# WordclockKopie.net
KiCad netlist of a schematic drawn in EAGLE
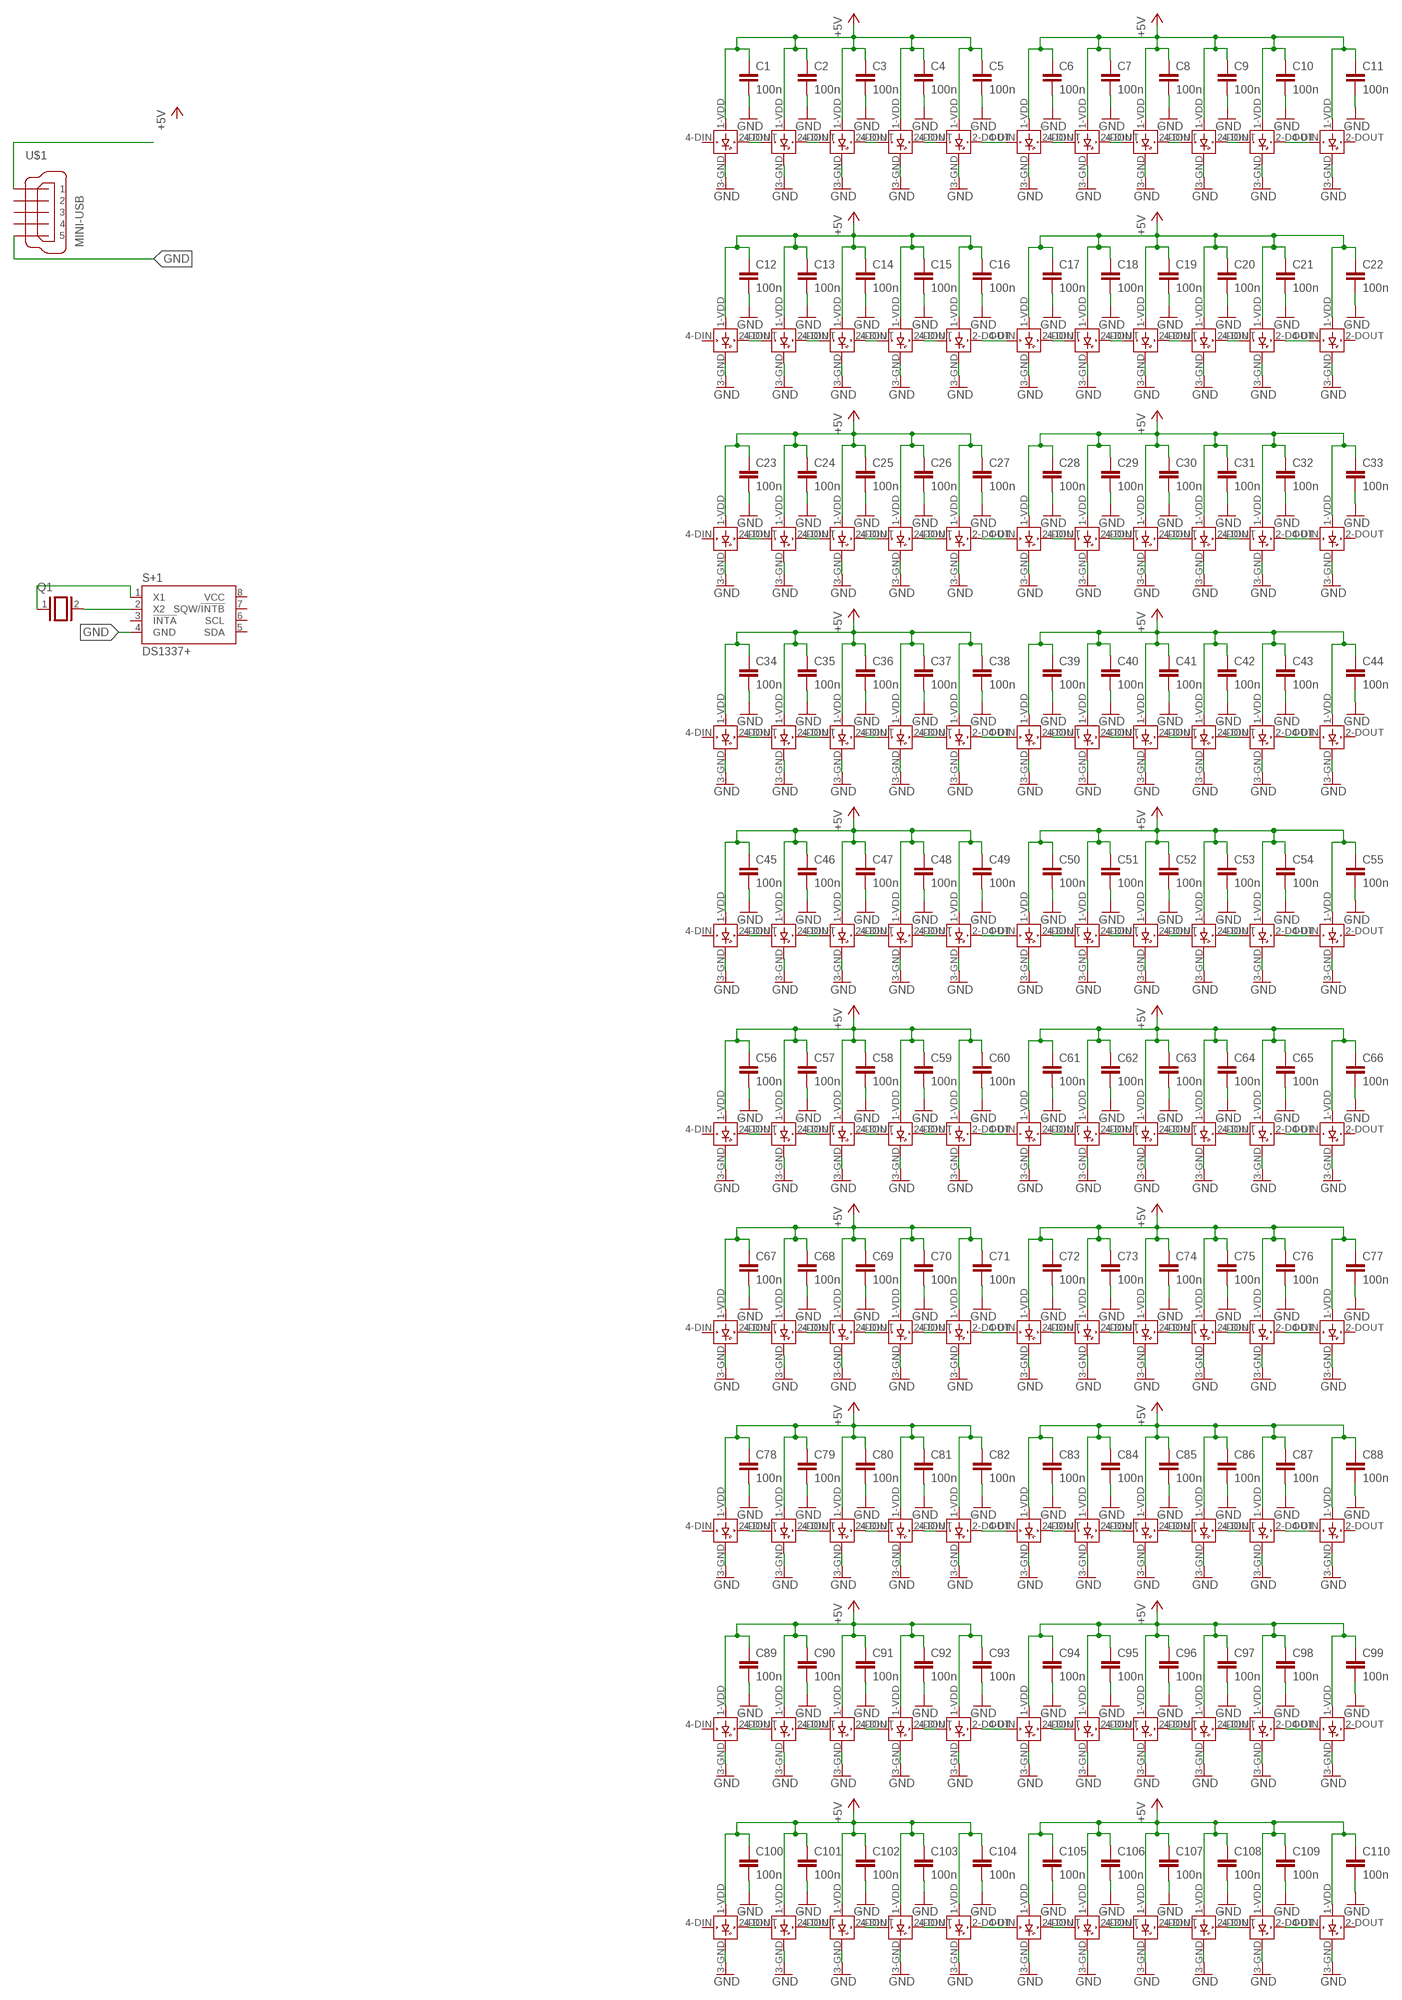
[diagram p0: schematic, sheet 1]

(export (version "E")
  (design (tool "Eeschema 10.0.6"))
  (components
    (comp (ref "C1")
      (value "100n")
      (footprint "eagle-import:C1310")
      (libsource (lib "eagle-import") (part "C-EUC1310"))
    )
    (comp (ref "C2")
      (value "100n")
      (footprint "eagle-import:C1310")
      (libsource (lib "eagle-import") (part "C-EUC1310"))
    )
    (comp (ref "C3")
      (value "100n")
      (footprint "eagle-import:C1310")
      (libsource (lib "eagle-import") (part "C-EUC1310"))
    )
    (comp (ref "C4")
      (value "100n")
      (footprint "eagle-import:C1310")
      (libsource (lib "eagle-import") (part "C-EUC1310"))
    )
    (comp (ref "C5")
      (value "100n")
      (footprint "eagle-import:C1310")
      (libsource (lib "eagle-import") (part "C-EUC1310"))
    )
    (comp (ref "C6")
      (value "100n")
      (footprint "eagle-import:C1310")
      (libsource (lib "eagle-import") (part "C-EUC1310"))
    )
    (comp (ref "C7")
      (value "100n")
      (footprint "eagle-import:C1310")
      (libsource (lib "eagle-import") (part "C-EUC1310"))
    )
    (comp (ref "C8")
      (value "100n")
      (footprint "eagle-import:C1310")
      (libsource (lib "eagle-import") (part "C-EUC1310"))
    )
    (comp (ref "C9")
      (value "100n")
      (footprint "eagle-import:C1310")
      (libsource (lib "eagle-import") (part "C-EUC1310"))
    )
    (comp (ref "C10")
      (value "100n")
      (footprint "eagle-import:C1310")
      (libsource (lib "eagle-import") (part "C-EUC1310"))
    )
    (comp (ref "C11")
      (value "100n")
      (footprint "eagle-import:C1310")
      (libsource (lib "eagle-import") (part "C-EUC1310"))
    )
    (comp (ref "C12")
      (value "100n")
      (footprint "eagle-import:C1310")
      (libsource (lib "eagle-import") (part "C-EUC1310"))
    )
    (comp (ref "C13")
      (value "100n")
      (footprint "eagle-import:C1310")
      (libsource (lib "eagle-import") (part "C-EUC1310"))
    )
    (comp (ref "C14")
      (value "100n")
      (footprint "eagle-import:C1310")
      (libsource (lib "eagle-import") (part "C-EUC1310"))
    )
    (comp (ref "C15")
      (value "100n")
      (footprint "eagle-import:C1310")
      (libsource (lib "eagle-import") (part "C-EUC1310"))
    )
    (comp (ref "C16")
      (value "100n")
      (footprint "eagle-import:C1310")
      (libsource (lib "eagle-import") (part "C-EUC1310"))
    )
    (comp (ref "C17")
      (value "100n")
      (footprint "eagle-import:C1310")
      (libsource (lib "eagle-import") (part "C-EUC1310"))
    )
    (comp (ref "C18")
      (value "100n")
      (footprint "eagle-import:C1310")
      (libsource (lib "eagle-import") (part "C-EUC1310"))
    )
    (comp (ref "C19")
      (value "100n")
      (footprint "eagle-import:C1310")
      (libsource (lib "eagle-import") (part "C-EUC1310"))
    )
    (comp (ref "C20")
      (value "100n")
      (footprint "eagle-import:C1310")
      (libsource (lib "eagle-import") (part "C-EUC1310"))
    )
    (comp (ref "C21")
      (value "100n")
      (footprint "eagle-import:C1310")
      (libsource (lib "eagle-import") (part "C-EUC1310"))
    )
    (comp (ref "C22")
      (value "100n")
      (footprint "eagle-import:C1310")
      (libsource (lib "eagle-import") (part "C-EUC1310"))
    )
    (comp (ref "C23")
      (value "100n")
      (footprint "eagle-import:C1310")
      (libsource (lib "eagle-import") (part "C-EUC1310"))
    )
    (comp (ref "C24")
      (value "100n")
      (footprint "eagle-import:C1310")
      (libsource (lib "eagle-import") (part "C-EUC1310"))
    )
    (comp (ref "C25")
      (value "100n")
      (footprint "eagle-import:C1310")
      (libsource (lib "eagle-import") (part "C-EUC1310"))
    )
    (comp (ref "C26")
      (value "100n")
      (footprint "eagle-import:C1310")
      (libsource (lib "eagle-import") (part "C-EUC1310"))
    )
    (comp (ref "C27")
      (value "100n")
      (footprint "eagle-import:C1310")
      (libsource (lib "eagle-import") (part "C-EUC1310"))
    )
    (comp (ref "C28")
      (value "100n")
      (footprint "eagle-import:C1310")
      (libsource (lib "eagle-import") (part "C-EUC1310"))
    )
    (comp (ref "C29")
      (value "100n")
      (footprint "eagle-import:C1310")
      (libsource (lib "eagle-import") (part "C-EUC1310"))
    )
    (comp (ref "C30")
      (value "100n")
      (footprint "eagle-import:C1310")
      (libsource (lib "eagle-import") (part "C-EUC1310"))
    )
    (comp (ref "C31")
      (value "100n")
      (footprint "eagle-import:C1310")
      (libsource (lib "eagle-import") (part "C-EUC1310"))
    )
    (comp (ref "C32")
      (value "100n")
      (footprint "eagle-import:C1310")
      (libsource (lib "eagle-import") (part "C-EUC1310"))
    )
    (comp (ref "C33")
      (value "100n")
      (footprint "eagle-import:C1310")
      (libsource (lib "eagle-import") (part "C-EUC1310"))
    )
    (comp (ref "C34")
      (value "100n")
      (footprint "eagle-import:C1310")
      (libsource (lib "eagle-import") (part "C-EUC1310"))
    )
    (comp (ref "C35")
      (value "100n")
      (footprint "eagle-import:C1310")
      (libsource (lib "eagle-import") (part "C-EUC1310"))
    )
    (comp (ref "C36")
      (value "100n")
      (footprint "eagle-import:C1310")
      (libsource (lib "eagle-import") (part "C-EUC1310"))
    )
    (comp (ref "C37")
      (value "100n")
      (footprint "eagle-import:C1310")
      (libsource (lib "eagle-import") (part "C-EUC1310"))
    )
    (comp (ref "C38")
      (value "100n")
      (footprint "eagle-import:C1310")
      (libsource (lib "eagle-import") (part "C-EUC1310"))
    )
    (comp (ref "C39")
      (value "100n")
      (footprint "eagle-import:C1310")
      (libsource (lib "eagle-import") (part "C-EUC1310"))
    )
    (comp (ref "C40")
      (value "100n")
      (footprint "eagle-import:C1310")
      (libsource (lib "eagle-import") (part "C-EUC1310"))
    )
    (comp (ref "C41")
      (value "100n")
      (footprint "eagle-import:C1310")
      (libsource (lib "eagle-import") (part "C-EUC1310"))
    )
    (comp (ref "C42")
      (value "100n")
      (footprint "eagle-import:C1310")
      (libsource (lib "eagle-import") (part "C-EUC1310"))
    )
    (comp (ref "C43")
      (value "100n")
      (footprint "eagle-import:C1310")
      (libsource (lib "eagle-import") (part "C-EUC1310"))
    )
    (comp (ref "C44")
      (value "100n")
      (footprint "eagle-import:C1310")
      (libsource (lib "eagle-import") (part "C-EUC1310"))
    )
    (comp (ref "C45")
      (value "100n")
      (footprint "eagle-import:C1310")
      (libsource (lib "eagle-import") (part "C-EUC1310"))
    )
    (comp (ref "C46")
      (value "100n")
      (footprint "eagle-import:C1310")
      (libsource (lib "eagle-import") (part "C-EUC1310"))
    )
    (comp (ref "C47")
      (value "100n")
      (footprint "eagle-import:C1310")
      (libsource (lib "eagle-import") (part "C-EUC1310"))
    )
    (comp (ref "C48")
      (value "100n")
      (footprint "eagle-import:C1310")
      (libsource (lib "eagle-import") (part "C-EUC1310"))
    )
    (comp (ref "C49")
      (value "100n")
      (footprint "eagle-import:C1310")
      (libsource (lib "eagle-import") (part "C-EUC1310"))
    )
    (comp (ref "C50")
      (value "100n")
      (footprint "eagle-import:C1310")
      (libsource (lib "eagle-import") (part "C-EUC1310"))
    )
    (comp (ref "C51")
      (value "100n")
      (footprint "eagle-import:C1310")
      (libsource (lib "eagle-import") (part "C-EUC1310"))
    )
    (comp (ref "C52")
      (value "100n")
      (footprint "eagle-import:C1310")
      (libsource (lib "eagle-import") (part "C-EUC1310"))
    )
    (comp (ref "C53")
      (value "100n")
      (footprint "eagle-import:C1310")
      (libsource (lib "eagle-import") (part "C-EUC1310"))
    )
    (comp (ref "C54")
      (value "100n")
      (footprint "eagle-import:C1310")
      (libsource (lib "eagle-import") (part "C-EUC1310"))
    )
    (comp (ref "C55")
      (value "100n")
      (footprint "eagle-import:C1310")
      (libsource (lib "eagle-import") (part "C-EUC1310"))
    )
    (comp (ref "C56")
      (value "100n")
      (footprint "eagle-import:C1310")
      (libsource (lib "eagle-import") (part "C-EUC1310"))
    )
    (comp (ref "C57")
      (value "100n")
      (footprint "eagle-import:C1310")
      (libsource (lib "eagle-import") (part "C-EUC1310"))
    )
    (comp (ref "C58")
      (value "100n")
      (footprint "eagle-import:C1310")
      (libsource (lib "eagle-import") (part "C-EUC1310"))
    )
    (comp (ref "C59")
      (value "100n")
      (footprint "eagle-import:C1310")
      (libsource (lib "eagle-import") (part "C-EUC1310"))
    )
    (comp (ref "C60")
      (value "100n")
      (footprint "eagle-import:C1310")
      (libsource (lib "eagle-import") (part "C-EUC1310"))
    )
    (comp (ref "C61")
      (value "100n")
      (footprint "eagle-import:C1310")
      (libsource (lib "eagle-import") (part "C-EUC1310"))
    )
    (comp (ref "C62")
      (value "100n")
      (footprint "eagle-import:C1310")
      (libsource (lib "eagle-import") (part "C-EUC1310"))
    )
    (comp (ref "C63")
      (value "100n")
      (footprint "eagle-import:C1310")
      (libsource (lib "eagle-import") (part "C-EUC1310"))
    )
    (comp (ref "C64")
      (value "100n")
      (footprint "eagle-import:C1310")
      (libsource (lib "eagle-import") (part "C-EUC1310"))
    )
    (comp (ref "C65")
      (value "100n")
      (footprint "eagle-import:C1310")
      (libsource (lib "eagle-import") (part "C-EUC1310"))
    )
    (comp (ref "C66")
      (value "100n")
      (footprint "eagle-import:C1310")
      (libsource (lib "eagle-import") (part "C-EUC1310"))
    )
    (comp (ref "C67")
      (value "100n")
      (footprint "eagle-import:C1310")
      (libsource (lib "eagle-import") (part "C-EUC1310"))
    )
    (comp (ref "C68")
      (value "100n")
      (footprint "eagle-import:C1310")
      (libsource (lib "eagle-import") (part "C-EUC1310"))
    )
    (comp (ref "C69")
      (value "100n")
      (footprint "eagle-import:C1310")
      (libsource (lib "eagle-import") (part "C-EUC1310"))
    )
    (comp (ref "C70")
      (value "100n")
      (footprint "eagle-import:C1310")
      (libsource (lib "eagle-import") (part "C-EUC1310"))
    )
    (comp (ref "C71")
      (value "100n")
      (footprint "eagle-import:C1310")
      (libsource (lib "eagle-import") (part "C-EUC1310"))
    )
    (comp (ref "C72")
      (value "100n")
      (footprint "eagle-import:C1310")
      (libsource (lib "eagle-import") (part "C-EUC1310"))
    )
    (comp (ref "C73")
      (value "100n")
      (footprint "eagle-import:C1310")
      (libsource (lib "eagle-import") (part "C-EUC1310"))
    )
    (comp (ref "C74")
      (value "100n")
      (footprint "eagle-import:C1310")
      (libsource (lib "eagle-import") (part "C-EUC1310"))
    )
    (comp (ref "C75")
      (value "100n")
      (footprint "eagle-import:C1310")
      (libsource (lib "eagle-import") (part "C-EUC1310"))
    )
    (comp (ref "C76")
      (value "100n")
      (footprint "eagle-import:C1310")
      (libsource (lib "eagle-import") (part "C-EUC1310"))
    )
    (comp (ref "C77")
      (value "100n")
      (footprint "eagle-import:C1310")
      (libsource (lib "eagle-import") (part "C-EUC1310"))
    )
    (comp (ref "C78")
      (value "100n")
      (footprint "eagle-import:C1310")
      (libsource (lib "eagle-import") (part "C-EUC1310"))
    )
    (comp (ref "C79")
      (value "100n")
      (footprint "eagle-import:C1310")
      (libsource (lib "eagle-import") (part "C-EUC1310"))
    )
    (comp (ref "C80")
      (value "100n")
      (footprint "eagle-import:C1310")
      (libsource (lib "eagle-import") (part "C-EUC1310"))
    )
    (comp (ref "C81")
      (value "100n")
      (footprint "eagle-import:C1310")
      (libsource (lib "eagle-import") (part "C-EUC1310"))
    )
    (comp (ref "C82")
      (value "100n")
      (footprint "eagle-import:C1310")
      (libsource (lib "eagle-import") (part "C-EUC1310"))
    )
    (comp (ref "C83")
      (value "100n")
      (footprint "eagle-import:C1310")
      (libsource (lib "eagle-import") (part "C-EUC1310"))
    )
    (comp (ref "C84")
      (value "100n")
      (footprint "eagle-import:C1310")
      (libsource (lib "eagle-import") (part "C-EUC1310"))
    )
    (comp (ref "C85")
      (value "100n")
      (footprint "eagle-import:C1310")
      (libsource (lib "eagle-import") (part "C-EUC1310"))
    )
    (comp (ref "C86")
      (value "100n")
      (footprint "eagle-import:C1310")
      (libsource (lib "eagle-import") (part "C-EUC1310"))
    )
    (comp (ref "C87")
      (value "100n")
      (footprint "eagle-import:C1310")
      (libsource (lib "eagle-import") (part "C-EUC1310"))
    )
    (comp (ref "C88")
      (value "100n")
      (footprint "eagle-import:C1310")
      (libsource (lib "eagle-import") (part "C-EUC1310"))
    )
    (comp (ref "C89")
      (value "100n")
      (footprint "eagle-import:C1310")
      (libsource (lib "eagle-import") (part "C-EUC1310"))
    )
    (comp (ref "C90")
      (value "100n")
      (footprint "eagle-import:C1310")
      (libsource (lib "eagle-import") (part "C-EUC1310"))
    )
    (comp (ref "C91")
      (value "100n")
      (footprint "eagle-import:C1310")
      (libsource (lib "eagle-import") (part "C-EUC1310"))
    )
    (comp (ref "C92")
      (value "100n")
      (footprint "eagle-import:C1310")
      (libsource (lib "eagle-import") (part "C-EUC1310"))
    )
    (comp (ref "C93")
      (value "100n")
      (footprint "eagle-import:C1310")
      (libsource (lib "eagle-import") (part "C-EUC1310"))
    )
    (comp (ref "C94")
      (value "100n")
      (footprint "eagle-import:C1310")
      (libsource (lib "eagle-import") (part "C-EUC1310"))
    )
    (comp (ref "C95")
      (value "100n")
      (footprint "eagle-import:C1310")
      (libsource (lib "eagle-import") (part "C-EUC1310"))
    )
    (comp (ref "C96")
      (value "100n")
      (footprint "eagle-import:C1310")
      (libsource (lib "eagle-import") (part "C-EUC1310"))
    )
    (comp (ref "C97")
      (value "100n")
      (footprint "eagle-import:C1310")
      (libsource (lib "eagle-import") (part "C-EUC1310"))
    )
    (comp (ref "C98")
      (value "100n")
      (footprint "eagle-import:C1310")
      (libsource (lib "eagle-import") (part "C-EUC1310"))
    )
    (comp (ref "C99")
      (value "100n")
      (footprint "eagle-import:C1310")
      (libsource (lib "eagle-import") (part "C-EUC1310"))
    )
    (comp (ref "C100")
      (value "100n")
      (footprint "eagle-import:C1310")
      (libsource (lib "eagle-import") (part "C-EUC1310"))
    )
    (comp (ref "C101")
      (value "100n")
      (footprint "eagle-import:C1310")
      (libsource (lib "eagle-import") (part "C-EUC1310"))
    )
    (comp (ref "C102")
      (value "100n")
      (footprint "eagle-import:C1310")
      (libsource (lib "eagle-import") (part "C-EUC1310"))
    )
    (comp (ref "C103")
      (value "100n")
      (footprint "eagle-import:C1310")
      (libsource (lib "eagle-import") (part "C-EUC1310"))
    )
    (comp (ref "C104")
      (value "100n")
      (footprint "eagle-import:C1310")
      (libsource (lib "eagle-import") (part "C-EUC1310"))
    )
    (comp (ref "C105")
      (value "100n")
      (footprint "eagle-import:C1310")
      (libsource (lib "eagle-import") (part "C-EUC1310"))
    )
    (comp (ref "C106")
      (value "100n")
      (footprint "eagle-import:C1310")
      (libsource (lib "eagle-import") (part "C-EUC1310"))
    )
    (comp (ref "C107")
      (value "100n")
      (footprint "eagle-import:C1310")
      (libsource (lib "eagle-import") (part "C-EUC1310"))
    )
    (comp (ref "C108")
      (value "100n")
      (footprint "eagle-import:C1310")
      (libsource (lib "eagle-import") (part "C-EUC1310"))
    )
    (comp (ref "C109")
      (value "100n")
      (footprint "eagle-import:C1310")
      (libsource (lib "eagle-import") (part "C-EUC1310"))
    )
    (comp (ref "C110")
      (value "100n")
      (footprint "eagle-import:C1310")
      (libsource (lib "eagle-import") (part "C-EUC1310"))
    )
    (comp (ref "L1")
      (value "WS2812B")
      (footprint "eagle-import:WS2812B")
      (libsource (lib "eagle-import") (part "WS2812B"))
    )
    (comp (ref "L2")
      (value "WS2812B")
      (footprint "eagle-import:WS2812B")
      (libsource (lib "eagle-import") (part "WS2812B"))
    )
    (comp (ref "L3")
      (value "WS2812B")
      (footprint "eagle-import:WS2812B")
      (libsource (lib "eagle-import") (part "WS2812B"))
    )
    (comp (ref "L4")
      (value "WS2812B")
      (footprint "eagle-import:WS2812B")
      (libsource (lib "eagle-import") (part "WS2812B"))
    )
    (comp (ref "L5")
      (value "WS2812B")
      (footprint "eagle-import:WS2812B")
      (libsource (lib "eagle-import") (part "WS2812B"))
    )
    (comp (ref "L6")
      (value "WS2812B")
      (footprint "eagle-import:WS2812B")
      (libsource (lib "eagle-import") (part "WS2812B"))
    )
    (comp (ref "L7")
      (value "WS2812B")
      (footprint "eagle-import:WS2812B")
      (libsource (lib "eagle-import") (part "WS2812B"))
    )
    (comp (ref "L8")
      (value "WS2812B")
      (footprint "eagle-import:WS2812B")
      (libsource (lib "eagle-import") (part "WS2812B"))
    )
    (comp (ref "L9")
      (value "WS2812B")
      (footprint "eagle-import:WS2812B")
      (libsource (lib "eagle-import") (part "WS2812B"))
    )
    (comp (ref "L10")
      (value "WS2812B")
      (footprint "eagle-import:WS2812B")
      (libsource (lib "eagle-import") (part "WS2812B"))
    )
    (comp (ref "L11")
      (value "WS2812B")
      (footprint "eagle-import:WS2812B")
      (libsource (lib "eagle-import") (part "WS2812B"))
    )
    (comp (ref "L12")
      (value "WS2812B")
      (footprint "eagle-import:WS2812B")
      (libsource (lib "eagle-import") (part "WS2812B"))
    )
    (comp (ref "L13")
      (value "WS2812B")
      (footprint "eagle-import:WS2812B")
      (libsource (lib "eagle-import") (part "WS2812B"))
    )
    (comp (ref "L14")
      (value "WS2812B")
      (footprint "eagle-import:WS2812B")
      (libsource (lib "eagle-import") (part "WS2812B"))
    )
    (comp (ref "L15")
      (value "WS2812B")
      (footprint "eagle-import:WS2812B")
      (libsource (lib "eagle-import") (part "WS2812B"))
    )
    (comp (ref "L16")
      (value "WS2812B")
      (footprint "eagle-import:WS2812B")
      (libsource (lib "eagle-import") (part "WS2812B"))
    )
    (comp (ref "L17")
      (value "WS2812B")
      (footprint "eagle-import:WS2812B")
      (libsource (lib "eagle-import") (part "WS2812B"))
    )
    (comp (ref "L18")
      (value "WS2812B")
      (footprint "eagle-import:WS2812B")
      (libsource (lib "eagle-import") (part "WS2812B"))
    )
    (comp (ref "L19")
      (value "WS2812B")
      (footprint "eagle-import:WS2812B")
      (libsource (lib "eagle-import") (part "WS2812B"))
    )
    (comp (ref "L20")
      (value "WS2812B")
      (footprint "eagle-import:WS2812B")
      (libsource (lib "eagle-import") (part "WS2812B"))
    )
    (comp (ref "L21")
      (value "WS2812B")
      (footprint "eagle-import:WS2812B")
      (libsource (lib "eagle-import") (part "WS2812B"))
    )
    (comp (ref "L22")
      (value "WS2812B")
      (footprint "eagle-import:WS2812B")
      (libsource (lib "eagle-import") (part "WS2812B"))
    )
    (comp (ref "L23")
      (value "WS2812B")
      (footprint "eagle-import:WS2812B")
      (libsource (lib "eagle-import") (part "WS2812B"))
    )
    (comp (ref "L24")
      (value "WS2812B")
      (footprint "eagle-import:WS2812B")
      (libsource (lib "eagle-import") (part "WS2812B"))
    )
    (comp (ref "L25")
      (value "WS2812B")
      (footprint "eagle-import:WS2812B")
      (libsource (lib "eagle-import") (part "WS2812B"))
    )
    (comp (ref "L26")
      (value "WS2812B")
      (footprint "eagle-import:WS2812B")
      (libsource (lib "eagle-import") (part "WS2812B"))
    )
    (comp (ref "L27")
      (value "WS2812B")
      (footprint "eagle-import:WS2812B")
      (libsource (lib "eagle-import") (part "WS2812B"))
    )
    (comp (ref "L28")
      (value "WS2812B")
      (footprint "eagle-import:WS2812B")
      (libsource (lib "eagle-import") (part "WS2812B"))
    )
    (comp (ref "L29")
      (value "WS2812B")
      (footprint "eagle-import:WS2812B")
      (libsource (lib "eagle-import") (part "WS2812B"))
    )
    (comp (ref "L30")
      (value "WS2812B")
      (footprint "eagle-import:WS2812B")
      (libsource (lib "eagle-import") (part "WS2812B"))
    )
    (comp (ref "L31")
      (value "WS2812B")
      (footprint "eagle-import:WS2812B")
      (libsource (lib "eagle-import") (part "WS2812B"))
    )
    (comp (ref "L32")
      (value "WS2812B")
      (footprint "eagle-import:WS2812B")
      (libsource (lib "eagle-import") (part "WS2812B"))
    )
    (comp (ref "L33")
      (value "WS2812B")
      (footprint "eagle-import:WS2812B")
      (libsource (lib "eagle-import") (part "WS2812B"))
    )
    (comp (ref "L34")
      (value "WS2812B")
      (footprint "eagle-import:WS2812B")
      (libsource (lib "eagle-import") (part "WS2812B"))
    )
    (comp (ref "L35")
      (value "WS2812B")
      (footprint "eagle-import:WS2812B")
      (libsource (lib "eagle-import") (part "WS2812B"))
    )
    (comp (ref "L36")
      (value "WS2812B")
      (footprint "eagle-import:WS2812B")
      (libsource (lib "eagle-import") (part "WS2812B"))
    )
    (comp (ref "L37")
      (value "WS2812B")
      (footprint "eagle-import:WS2812B")
      (libsource (lib "eagle-import") (part "WS2812B"))
    )
    (comp (ref "L38")
      (value "WS2812B")
      (footprint "eagle-import:WS2812B")
      (libsource (lib "eagle-import") (part "WS2812B"))
    )
    (comp (ref "L39")
      (value "WS2812B")
      (footprint "eagle-import:WS2812B")
      (libsource (lib "eagle-import") (part "WS2812B"))
    )
    (comp (ref "L40")
      (value "WS2812B")
      (footprint "eagle-import:WS2812B")
      (libsource (lib "eagle-import") (part "WS2812B"))
    )
    (comp (ref "L41")
      (value "WS2812B")
      (footprint "eagle-import:WS2812B")
      (libsource (lib "eagle-import") (part "WS2812B"))
    )
    (comp (ref "L42")
      (value "WS2812B")
      (footprint "eagle-import:WS2812B")
      (libsource (lib "eagle-import") (part "WS2812B"))
    )
    (comp (ref "L43")
      (value "WS2812B")
      (footprint "eagle-import:WS2812B")
      (libsource (lib "eagle-import") (part "WS2812B"))
    )
    (comp (ref "L44")
      (value "WS2812B")
      (footprint "eagle-import:WS2812B")
      (libsource (lib "eagle-import") (part "WS2812B"))
    )
    (comp (ref "L45")
      (value "WS2812B")
      (footprint "eagle-import:WS2812B")
      (libsource (lib "eagle-import") (part "WS2812B"))
    )
    (comp (ref "L46")
      (value "WS2812B")
      (footprint "eagle-import:WS2812B")
      (libsource (lib "eagle-import") (part "WS2812B"))
    )
    (comp (ref "L47")
      (value "WS2812B")
      (footprint "eagle-import:WS2812B")
      (libsource (lib "eagle-import") (part "WS2812B"))
    )
    (comp (ref "L48")
      (value "WS2812B")
      (footprint "eagle-import:WS2812B")
      (libsource (lib "eagle-import") (part "WS2812B"))
    )
    (comp (ref "L49")
      (value "WS2812B")
      (footprint "eagle-import:WS2812B")
      (libsource (lib "eagle-import") (part "WS2812B"))
    )
    (comp (ref "L50")
      (value "WS2812B")
      (footprint "eagle-import:WS2812B")
      (libsource (lib "eagle-import") (part "WS2812B"))
    )
    (comp (ref "L51")
      (value "WS2812B")
      (footprint "eagle-import:WS2812B")
      (libsource (lib "eagle-import") (part "WS2812B"))
    )
    (comp (ref "L52")
      (value "WS2812B")
      (footprint "eagle-import:WS2812B")
      (libsource (lib "eagle-import") (part "WS2812B"))
    )
    (comp (ref "L53")
      (value "WS2812B")
      (footprint "eagle-import:WS2812B")
      (libsource (lib "eagle-import") (part "WS2812B"))
    )
    (comp (ref "L54")
      (value "WS2812B")
      (footprint "eagle-import:WS2812B")
      (libsource (lib "eagle-import") (part "WS2812B"))
    )
    (comp (ref "L55")
      (value "WS2812B")
      (footprint "eagle-import:WS2812B")
      (libsource (lib "eagle-import") (part "WS2812B"))
    )
    (comp (ref "L56")
      (value "WS2812B")
      (footprint "eagle-import:WS2812B")
      (libsource (lib "eagle-import") (part "WS2812B"))
    )
    (comp (ref "L57")
      (value "WS2812B")
      (footprint "eagle-import:WS2812B")
      (libsource (lib "eagle-import") (part "WS2812B"))
    )
    (comp (ref "L58")
      (value "WS2812B")
      (footprint "eagle-import:WS2812B")
      (libsource (lib "eagle-import") (part "WS2812B"))
    )
    (comp (ref "L59")
      (value "WS2812B")
      (footprint "eagle-import:WS2812B")
      (libsource (lib "eagle-import") (part "WS2812B"))
    )
    (comp (ref "L60")
      (value "WS2812B")
      (footprint "eagle-import:WS2812B")
      (libsource (lib "eagle-import") (part "WS2812B"))
    )
    (comp (ref "L61")
      (value "WS2812B")
      (footprint "eagle-import:WS2812B")
      (libsource (lib "eagle-import") (part "WS2812B"))
    )
    (comp (ref "L62")
      (value "WS2812B")
      (footprint "eagle-import:WS2812B")
      (libsource (lib "eagle-import") (part "WS2812B"))
    )
    (comp (ref "L63")
      (value "WS2812B")
      (footprint "eagle-import:WS2812B")
      (libsource (lib "eagle-import") (part "WS2812B"))
    )
    (comp (ref "L64")
      (value "WS2812B")
      (footprint "eagle-import:WS2812B")
      (libsource (lib "eagle-import") (part "WS2812B"))
    )
    (comp (ref "L65")
      (value "WS2812B")
      (footprint "eagle-import:WS2812B")
      (libsource (lib "eagle-import") (part "WS2812B"))
    )
    (comp (ref "L66")
      (value "WS2812B")
      (footprint "eagle-import:WS2812B")
      (libsource (lib "eagle-import") (part "WS2812B"))
    )
    (comp (ref "L67")
      (value "WS2812B")
      (footprint "eagle-import:WS2812B")
      (libsource (lib "eagle-import") (part "WS2812B"))
    )
    (comp (ref "L68")
      (value "WS2812B")
      (footprint "eagle-import:WS2812B")
      (libsource (lib "eagle-import") (part "WS2812B"))
    )
    (comp (ref "L69")
      (value "WS2812B")
      (footprint "eagle-import:WS2812B")
      (libsource (lib "eagle-import") (part "WS2812B"))
    )
    (comp (ref "L70")
      (value "WS2812B")
      (footprint "eagle-import:WS2812B")
      (libsource (lib "eagle-import") (part "WS2812B"))
    )
    (comp (ref "L71")
      (value "WS2812B")
      (footprint "eagle-import:WS2812B")
      (libsource (lib "eagle-import") (part "WS2812B"))
    )
    (comp (ref "L72")
      (value "WS2812B")
      (footprint "eagle-import:WS2812B")
      (libsource (lib "eagle-import") (part "WS2812B"))
    )
    (comp (ref "L73")
      (value "WS2812B")
      (footprint "eagle-import:WS2812B")
      (libsource (lib "eagle-import") (part "WS2812B"))
    )
    (comp (ref "L74")
      (value "WS2812B")
      (footprint "eagle-import:WS2812B")
      (libsource (lib "eagle-import") (part "WS2812B"))
    )
    (comp (ref "L75")
      (value "WS2812B")
      (footprint "eagle-import:WS2812B")
      (libsource (lib "eagle-import") (part "WS2812B"))
    )
    (comp (ref "L76")
      (value "WS2812B")
      (footprint "eagle-import:WS2812B")
      (libsource (lib "eagle-import") (part "WS2812B"))
    )
    (comp (ref "L77")
      (value "WS2812B")
      (footprint "eagle-import:WS2812B")
      (libsource (lib "eagle-import") (part "WS2812B"))
    )
    (comp (ref "L78")
      (value "WS2812B")
      (footprint "eagle-import:WS2812B")
      (libsource (lib "eagle-import") (part "WS2812B"))
    )
    (comp (ref "L79")
      (value "WS2812B")
      (footprint "eagle-import:WS2812B")
      (libsource (lib "eagle-import") (part "WS2812B"))
    )
    (comp (ref "L80")
      (value "WS2812B")
      (footprint "eagle-import:WS2812B")
      (libsource (lib "eagle-import") (part "WS2812B"))
    )
    (comp (ref "L81")
      (value "WS2812B")
      (footprint "eagle-import:WS2812B")
      (libsource (lib "eagle-import") (part "WS2812B"))
    )
    (comp (ref "L82")
      (value "WS2812B")
      (footprint "eagle-import:WS2812B")
      (libsource (lib "eagle-import") (part "WS2812B"))
    )
    (comp (ref "L83")
      (value "WS2812B")
      (footprint "eagle-import:WS2812B")
      (libsource (lib "eagle-import") (part "WS2812B"))
    )
    (comp (ref "L84")
      (value "WS2812B")
      (footprint "eagle-import:WS2812B")
      (libsource (lib "eagle-import") (part "WS2812B"))
    )
    (comp (ref "L85")
      (value "WS2812B")
      (footprint "eagle-import:WS2812B")
      (libsource (lib "eagle-import") (part "WS2812B"))
    )
    (comp (ref "L86")
      (value "WS2812B")
      (footprint "eagle-import:WS2812B")
      (libsource (lib "eagle-import") (part "WS2812B"))
    )
    (comp (ref "L87")
      (value "WS2812B")
      (footprint "eagle-import:WS2812B")
      (libsource (lib "eagle-import") (part "WS2812B"))
    )
    (comp (ref "L88")
      (value "WS2812B")
      (footprint "eagle-import:WS2812B")
      (libsource (lib "eagle-import") (part "WS2812B"))
    )
    (comp (ref "L89")
      (value "WS2812B")
      (footprint "eagle-import:WS2812B")
      (libsource (lib "eagle-import") (part "WS2812B"))
    )
    (comp (ref "L90")
      (value "WS2812B")
      (footprint "eagle-import:WS2812B")
      (libsource (lib "eagle-import") (part "WS2812B"))
    )
    (comp (ref "L91")
      (value "WS2812B")
      (footprint "eagle-import:WS2812B")
      (libsource (lib "eagle-import") (part "WS2812B"))
    )
    (comp (ref "L92")
      (value "WS2812B")
      (footprint "eagle-import:WS2812B")
      (libsource (lib "eagle-import") (part "WS2812B"))
    )
    (comp (ref "L93")
      (value "WS2812B")
      (footprint "eagle-import:WS2812B")
      (libsource (lib "eagle-import") (part "WS2812B"))
    )
    (comp (ref "L94")
      (value "WS2812B")
      (footprint "eagle-import:WS2812B")
      (libsource (lib "eagle-import") (part "WS2812B"))
    )
    (comp (ref "L95")
      (value "WS2812B")
      (footprint "eagle-import:WS2812B")
      (libsource (lib "eagle-import") (part "WS2812B"))
    )
    (comp (ref "L96")
      (value "WS2812B")
      (footprint "eagle-import:WS2812B")
      (libsource (lib "eagle-import") (part "WS2812B"))
    )
    (comp (ref "L97")
      (value "WS2812B")
      (footprint "eagle-import:WS2812B")
      (libsource (lib "eagle-import") (part "WS2812B"))
    )
    (comp (ref "L98")
      (value "WS2812B")
      (footprint "eagle-import:WS2812B")
      (libsource (lib "eagle-import") (part "WS2812B"))
    )
    (comp (ref "L99")
      (value "WS2812B")
      (footprint "eagle-import:WS2812B")
      (libsource (lib "eagle-import") (part "WS2812B"))
    )
    (comp (ref "L100")
      (value "WS2812B")
      (footprint "eagle-import:WS2812B")
      (libsource (lib "eagle-import") (part "WS2812B"))
    )
    (comp (ref "L101")
      (value "WS2812B")
      (footprint "eagle-import:WS2812B")
      (libsource (lib "eagle-import") (part "WS2812B"))
    )
    (comp (ref "L102")
      (value "WS2812B")
      (footprint "eagle-import:WS2812B")
      (libsource (lib "eagle-import") (part "WS2812B"))
    )
    (comp (ref "L103")
      (value "WS2812B")
      (footprint "eagle-import:WS2812B")
      (libsource (lib "eagle-import") (part "WS2812B"))
    )
    (comp (ref "L104")
      (value "WS2812B")
      (footprint "eagle-import:WS2812B")
      (libsource (lib "eagle-import") (part "WS2812B"))
    )
    (comp (ref "L105")
      (value "WS2812B")
      (footprint "eagle-import:WS2812B")
      (libsource (lib "eagle-import") (part "WS2812B"))
    )
    (comp (ref "L106")
      (value "WS2812B")
      (footprint "eagle-import:WS2812B")
      (libsource (lib "eagle-import") (part "WS2812B"))
    )
    (comp (ref "L107")
      (value "WS2812B")
      (footprint "eagle-import:WS2812B")
      (libsource (lib "eagle-import") (part "WS2812B"))
    )
    (comp (ref "L108")
      (value "WS2812B")
      (footprint "eagle-import:WS2812B")
      (libsource (lib "eagle-import") (part "WS2812B"))
    )
    (comp (ref "L109")
      (value "WS2812B")
      (footprint "eagle-import:WS2812B")
      (libsource (lib "eagle-import") (part "WS2812B"))
    )
    (comp (ref "L110")
      (value "WS2812B")
      (footprint "eagle-import:WS2812B")
      (libsource (lib "eagle-import") (part "WS2812B"))
    )
    (comp (ref "Q1")
      (value "XTAL")
      (footprint "eagle-import:Q")
      (libsource (lib "eagle-import") (part "XTAL"))
    )
    (comp (ref "S+1")
      (value "DS1337+")
      (footprint "eagle-import:DIL8")
      (libsource (lib "eagle-import") (part "DS1337+"))
    )
    (comp (ref "U$1")
      (value "MINI-USB")
      (footprint "eagle-import:MINI-USB")
      (libsource (lib "eagle-import") (part "MINI-USB"))
    )
  )
  (nets
    (net (code "1") (name "+5V") (class "Default")
      (node (ref "C1") (pin "1") (pinfunction "1_1") (pintype "passive"))
      (node (ref "C10") (pin "1") (pinfunction "1_1") (pintype "passive"))
      (node (ref "C100") (pin "1") (pinfunction "1_1") (pintype "passive"))
      (node (ref "C101") (pin "1") (pinfunction "1_1") (pintype "passive"))
      (node (ref "C102") (pin "1") (pinfunction "1_1") (pintype "passive"))
      (node (ref "C103") (pin "1") (pinfunction "1_1") (pintype "passive"))
      (node (ref "C104") (pin "1") (pinfunction "1_1") (pintype "passive"))
      (node (ref "C105") (pin "1") (pinfunction "1_1") (pintype "passive"))
      (node (ref "C106") (pin "1") (pinfunction "1_1") (pintype "passive"))
      (node (ref "C107") (pin "1") (pinfunction "1_1") (pintype "passive"))
      (node (ref "C108") (pin "1") (pinfunction "1_1") (pintype "passive"))
      (node (ref "C109") (pin "1") (pinfunction "1_1") (pintype "passive"))
      (node (ref "C11") (pin "1") (pinfunction "1_1") (pintype "passive"))
      (node (ref "C110") (pin "1") (pinfunction "1_1") (pintype "passive"))
      (node (ref "C12") (pin "1") (pinfunction "1_1") (pintype "passive"))
      (node (ref "C13") (pin "1") (pinfunction "1_1") (pintype "passive"))
      (node (ref "C14") (pin "1") (pinfunction "1_1") (pintype "passive"))
      (node (ref "C15") (pin "1") (pinfunction "1_1") (pintype "passive"))
      (node (ref "C16") (pin "1") (pinfunction "1_1") (pintype "passive"))
      (node (ref "C17") (pin "1") (pinfunction "1_1") (pintype "passive"))
      (node (ref "C18") (pin "1") (pinfunction "1_1") (pintype "passive"))
      (node (ref "C19") (pin "1") (pinfunction "1_1") (pintype "passive"))
      (node (ref "C2") (pin "1") (pinfunction "1_1") (pintype "passive"))
      (node (ref "C20") (pin "1") (pinfunction "1_1") (pintype "passive"))
      (node (ref "C21") (pin "1") (pinfunction "1_1") (pintype "passive"))
      (node (ref "C22") (pin "1") (pinfunction "1_1") (pintype "passive"))
      (node (ref "C23") (pin "1") (pinfunction "1_1") (pintype "passive"))
      (node (ref "C24") (pin "1") (pinfunction "1_1") (pintype "passive"))
      (node (ref "C25") (pin "1") (pinfunction "1_1") (pintype "passive"))
      (node (ref "C26") (pin "1") (pinfunction "1_1") (pintype "passive"))
      (node (ref "C27") (pin "1") (pinfunction "1_1") (pintype "passive"))
      (node (ref "C28") (pin "1") (pinfunction "1_1") (pintype "passive"))
      (node (ref "C29") (pin "1") (pinfunction "1_1") (pintype "passive"))
      (node (ref "C3") (pin "1") (pinfunction "1_1") (pintype "passive"))
      (node (ref "C30") (pin "1") (pinfunction "1_1") (pintype "passive"))
      (node (ref "C31") (pin "1") (pinfunction "1_1") (pintype "passive"))
      (node (ref "C32") (pin "1") (pinfunction "1_1") (pintype "passive"))
      (node (ref "C33") (pin "1") (pinfunction "1_1") (pintype "passive"))
      (node (ref "C34") (pin "1") (pinfunction "1_1") (pintype "passive"))
      (node (ref "C35") (pin "1") (pinfunction "1_1") (pintype "passive"))
      (node (ref "C36") (pin "1") (pinfunction "1_1") (pintype "passive"))
      (node (ref "C37") (pin "1") (pinfunction "1_1") (pintype "passive"))
      (node (ref "C38") (pin "1") (pinfunction "1_1") (pintype "passive"))
      (node (ref "C39") (pin "1") (pinfunction "1_1") (pintype "passive"))
      (node (ref "C4") (pin "1") (pinfunction "1_1") (pintype "passive"))
      (node (ref "C40") (pin "1") (pinfunction "1_1") (pintype "passive"))
      (node (ref "C41") (pin "1") (pinfunction "1_1") (pintype "passive"))
      (node (ref "C42") (pin "1") (pinfunction "1_1") (pintype "passive"))
      (node (ref "C43") (pin "1") (pinfunction "1_1") (pintype "passive"))
      (node (ref "C44") (pin "1") (pinfunction "1_1") (pintype "passive"))
      (node (ref "C45") (pin "1") (pinfunction "1_1") (pintype "passive"))
      (node (ref "C46") (pin "1") (pinfunction "1_1") (pintype "passive"))
      (node (ref "C47") (pin "1") (pinfunction "1_1") (pintype "passive"))
      (node (ref "C48") (pin "1") (pinfunction "1_1") (pintype "passive"))
      (node (ref "C49") (pin "1") (pinfunction "1_1") (pintype "passive"))
      (node (ref "C5") (pin "1") (pinfunction "1_1") (pintype "passive"))
      (node (ref "C50") (pin "1") (pinfunction "1_1") (pintype "passive"))
      (node (ref "C51") (pin "1") (pinfunction "1_1") (pintype "passive"))
      (node (ref "C52") (pin "1") (pinfunction "1_1") (pintype "passive"))
      (node (ref "C53") (pin "1") (pinfunction "1_1") (pintype "passive"))
      (node (ref "C54") (pin "1") (pinfunction "1_1") (pintype "passive"))
      (node (ref "C55") (pin "1") (pinfunction "1_1") (pintype "passive"))
      (node (ref "C56") (pin "1") (pinfunction "1_1") (pintype "passive"))
      (node (ref "C57") (pin "1") (pinfunction "1_1") (pintype "passive"))
      (node (ref "C58") (pin "1") (pinfunction "1_1") (pintype "passive"))
      (node (ref "C59") (pin "1") (pinfunction "1_1") (pintype "passive"))
      (node (ref "C6") (pin "1") (pinfunction "1_1") (pintype "passive"))
      (node (ref "C60") (pin "1") (pinfunction "1_1") (pintype "passive"))
      (node (ref "C61") (pin "1") (pinfunction "1_1") (pintype "passive"))
      (node (ref "C62") (pin "1") (pinfunction "1_1") (pintype "passive"))
      (node (ref "C63") (pin "1") (pinfunction "1_1") (pintype "passive"))
      (node (ref "C64") (pin "1") (pinfunction "1_1") (pintype "passive"))
      (node (ref "C65") (pin "1") (pinfunction "1_1") (pintype "passive"))
      (node (ref "C66") (pin "1") (pinfunction "1_1") (pintype "passive"))
      (node (ref "C67") (pin "1") (pinfunction "1_1") (pintype "passive"))
      (node (ref "C68") (pin "1") (pinfunction "1_1") (pintype "passive"))
      (node (ref "C69") (pin "1") (pinfunction "1_1") (pintype "passive"))
      (node (ref "C7") (pin "1") (pinfunction "1_1") (pintype "passive"))
      (node (ref "C70") (pin "1") (pinfunction "1_1") (pintype "passive"))
      (node (ref "C71") (pin "1") (pinfunction "1_1") (pintype "passive"))
      (node (ref "C72") (pin "1") (pinfunction "1_1") (pintype "passive"))
      (node (ref "C73") (pin "1") (pinfunction "1_1") (pintype "passive"))
      (node (ref "C74") (pin "1") (pinfunction "1_1") (pintype "passive"))
      (node (ref "C75") (pin "1") (pinfunction "1_1") (pintype "passive"))
      (node (ref "C76") (pin "1") (pinfunction "1_1") (pintype "passive"))
      (node (ref "C77") (pin "1") (pinfunction "1_1") (pintype "passive"))
      (node (ref "C78") (pin "1") (pinfunction "1_1") (pintype "passive"))
      (node (ref "C79") (pin "1") (pinfunction "1_1") (pintype "passive"))
      (node (ref "C8") (pin "1") (pinfunction "1_1") (pintype "passive"))
      (node (ref "C80") (pin "1") (pinfunction "1_1") (pintype "passive"))
      (node (ref "C81") (pin "1") (pinfunction "1_1") (pintype "passive"))
      (node (ref "C82") (pin "1") (pinfunction "1_1") (pintype "passive"))
      (node (ref "C83") (pin "1") (pinfunction "1_1") (pintype "passive"))
      (node (ref "C84") (pin "1") (pinfunction "1_1") (pintype "passive"))
      (node (ref "C85") (pin "1") (pinfunction "1_1") (pintype "passive"))
      (node (ref "C86") (pin "1") (pinfunction "1_1") (pintype "passive"))
      (node (ref "C87") (pin "1") (pinfunction "1_1") (pintype "passive"))
      (node (ref "C88") (pin "1") (pinfunction "1_1") (pintype "passive"))
      (node (ref "C89") (pin "1") (pinfunction "1_1") (pintype "passive"))
      (node (ref "C9") (pin "1") (pinfunction "1_1") (pintype "passive"))
      (node (ref "C90") (pin "1") (pinfunction "1_1") (pintype "passive"))
      (node (ref "C91") (pin "1") (pinfunction "1_1") (pintype "passive"))
      (node (ref "C92") (pin "1") (pinfunction "1_1") (pintype "passive"))
      (node (ref "C93") (pin "1") (pinfunction "1_1") (pintype "passive"))
      (node (ref "C94") (pin "1") (pinfunction "1_1") (pintype "passive"))
      (node (ref "C95") (pin "1") (pinfunction "1_1") (pintype "passive"))
      (node (ref "C96") (pin "1") (pinfunction "1_1") (pintype "passive"))
      (node (ref "C97") (pin "1") (pinfunction "1_1") (pintype "passive"))
      (node (ref "C98") (pin "1") (pinfunction "1_1") (pintype "passive"))
      (node (ref "C99") (pin "1") (pinfunction "1_1") (pintype "passive"))
      (node (ref "L1") (pin "1-VDD") (pinfunction "VDD_1-VDD") (pintype "bidirectional"))
      (node (ref "L10") (pin "1-VDD") (pinfunction "VDD_1-VDD") (pintype "bidirectional"))
      (node (ref "L100") (pin "1-VDD") (pinfunction "VDD_1-VDD") (pintype "bidirectional"))
      (node (ref "L101") (pin "1-VDD") (pinfunction "VDD_1-VDD") (pintype "bidirectional"))
      (node (ref "L102") (pin "1-VDD") (pinfunction "VDD_1-VDD") (pintype "bidirectional"))
      (node (ref "L103") (pin "1-VDD") (pinfunction "VDD_1-VDD") (pintype "bidirectional"))
      (node (ref "L104") (pin "1-VDD") (pinfunction "VDD_1-VDD") (pintype "bidirectional"))
      (node (ref "L105") (pin "1-VDD") (pinfunction "VDD_1-VDD") (pintype "bidirectional"))
      (node (ref "L106") (pin "1-VDD") (pinfunction "VDD_1-VDD") (pintype "bidirectional"))
      (node (ref "L107") (pin "1-VDD") (pinfunction "VDD_1-VDD") (pintype "bidirectional"))
      (node (ref "L108") (pin "1-VDD") (pinfunction "VDD_1-VDD") (pintype "bidirectional"))
      (node (ref "L109") (pin "1-VDD") (pinfunction "VDD_1-VDD") (pintype "bidirectional"))
      (node (ref "L11") (pin "1-VDD") (pinfunction "VDD_1-VDD") (pintype "bidirectional"))
      (node (ref "L110") (pin "1-VDD") (pinfunction "VDD_1-VDD") (pintype "bidirectional"))
      (node (ref "L12") (pin "1-VDD") (pinfunction "VDD_1-VDD") (pintype "bidirectional"))
      (node (ref "L13") (pin "1-VDD") (pinfunction "VDD_1-VDD") (pintype "bidirectional"))
      (node (ref "L14") (pin "1-VDD") (pinfunction "VDD_1-VDD") (pintype "bidirectional"))
      (node (ref "L15") (pin "1-VDD") (pinfunction "VDD_1-VDD") (pintype "bidirectional"))
      (node (ref "L16") (pin "1-VDD") (pinfunction "VDD_1-VDD") (pintype "bidirectional"))
      (node (ref "L17") (pin "1-VDD") (pinfunction "VDD_1-VDD") (pintype "bidirectional"))
      (node (ref "L18") (pin "1-VDD") (pinfunction "VDD_1-VDD") (pintype "bidirectional"))
      (node (ref "L19") (pin "1-VDD") (pinfunction "VDD_1-VDD") (pintype "bidirectional"))
      (node (ref "L2") (pin "1-VDD") (pinfunction "VDD_1-VDD") (pintype "bidirectional"))
      (node (ref "L20") (pin "1-VDD") (pinfunction "VDD_1-VDD") (pintype "bidirectional"))
      (node (ref "L21") (pin "1-VDD") (pinfunction "VDD_1-VDD") (pintype "bidirectional"))
      (node (ref "L22") (pin "1-VDD") (pinfunction "VDD_1-VDD") (pintype "bidirectional"))
      (node (ref "L23") (pin "1-VDD") (pinfunction "VDD_1-VDD") (pintype "bidirectional"))
      (node (ref "L24") (pin "1-VDD") (pinfunction "VDD_1-VDD") (pintype "bidirectional"))
      (node (ref "L25") (pin "1-VDD") (pinfunction "VDD_1-VDD") (pintype "bidirectional"))
      (node (ref "L26") (pin "1-VDD") (pinfunction "VDD_1-VDD") (pintype "bidirectional"))
      (node (ref "L27") (pin "1-VDD") (pinfunction "VDD_1-VDD") (pintype "bidirectional"))
      (node (ref "L28") (pin "1-VDD") (pinfunction "VDD_1-VDD") (pintype "bidirectional"))
      (node (ref "L29") (pin "1-VDD") (pinfunction "VDD_1-VDD") (pintype "bidirectional"))
      (node (ref "L3") (pin "1-VDD") (pinfunction "VDD_1-VDD") (pintype "bidirectional"))
      (node (ref "L30") (pin "1-VDD") (pinfunction "VDD_1-VDD") (pintype "bidirectional"))
      (node (ref "L31") (pin "1-VDD") (pinfunction "VDD_1-VDD") (pintype "bidirectional"))
      (node (ref "L32") (pin "1-VDD") (pinfunction "VDD_1-VDD") (pintype "bidirectional"))
      (node (ref "L33") (pin "1-VDD") (pinfunction "VDD_1-VDD") (pintype "bidirectional"))
      (node (ref "L34") (pin "1-VDD") (pinfunction "VDD_1-VDD") (pintype "bidirectional"))
      (node (ref "L35") (pin "1-VDD") (pinfunction "VDD_1-VDD") (pintype "bidirectional"))
      (node (ref "L36") (pin "1-VDD") (pinfunction "VDD_1-VDD") (pintype "bidirectional"))
      (node (ref "L37") (pin "1-VDD") (pinfunction "VDD_1-VDD") (pintype "bidirectional"))
      (node (ref "L38") (pin "1-VDD") (pinfunction "VDD_1-VDD") (pintype "bidirectional"))
      (node (ref "L39") (pin "1-VDD") (pinfunction "VDD_1-VDD") (pintype "bidirectional"))
      (node (ref "L4") (pin "1-VDD") (pinfunction "VDD_1-VDD") (pintype "bidirectional"))
      (node (ref "L40") (pin "1-VDD") (pinfunction "VDD_1-VDD") (pintype "bidirectional"))
      (node (ref "L41") (pin "1-VDD") (pinfunction "VDD_1-VDD") (pintype "bidirectional"))
      (node (ref "L42") (pin "1-VDD") (pinfunction "VDD_1-VDD") (pintype "bidirectional"))
      (node (ref "L43") (pin "1-VDD") (pinfunction "VDD_1-VDD") (pintype "bidirectional"))
      (node (ref "L44") (pin "1-VDD") (pinfunction "VDD_1-VDD") (pintype "bidirectional"))
      (node (ref "L45") (pin "1-VDD") (pinfunction "VDD_1-VDD") (pintype "bidirectional"))
      (node (ref "L46") (pin "1-VDD") (pinfunction "VDD_1-VDD") (pintype "bidirectional"))
      (node (ref "L47") (pin "1-VDD") (pinfunction "VDD_1-VDD") (pintype "bidirectional"))
      (node (ref "L48") (pin "1-VDD") (pinfunction "VDD_1-VDD") (pintype "bidirectional"))
      (node (ref "L49") (pin "1-VDD") (pinfunction "VDD_1-VDD") (pintype "bidirectional"))
      (node (ref "L5") (pin "1-VDD") (pinfunction "VDD_1-VDD") (pintype "bidirectional"))
      (node (ref "L50") (pin "1-VDD") (pinfunction "VDD_1-VDD") (pintype "bidirectional"))
      (node (ref "L51") (pin "1-VDD") (pinfunction "VDD_1-VDD") (pintype "bidirectional"))
      (node (ref "L52") (pin "1-VDD") (pinfunction "VDD_1-VDD") (pintype "bidirectional"))
      (node (ref "L53") (pin "1-VDD") (pinfunction "VDD_1-VDD") (pintype "bidirectional"))
      (node (ref "L54") (pin "1-VDD") (pinfunction "VDD_1-VDD") (pintype "bidirectional"))
      (node (ref "L55") (pin "1-VDD") (pinfunction "VDD_1-VDD") (pintype "bidirectional"))
      (node (ref "L56") (pin "1-VDD") (pinfunction "VDD_1-VDD") (pintype "bidirectional"))
      (node (ref "L57") (pin "1-VDD") (pinfunction "VDD_1-VDD") (pintype "bidirectional"))
      (node (ref "L58") (pin "1-VDD") (pinfunction "VDD_1-VDD") (pintype "bidirectional"))
      (node (ref "L59") (pin "1-VDD") (pinfunction "VDD_1-VDD") (pintype "bidirectional"))
      (node (ref "L6") (pin "1-VDD") (pinfunction "VDD_1-VDD") (pintype "bidirectional"))
      (node (ref "L60") (pin "1-VDD") (pinfunction "VDD_1-VDD") (pintype "bidirectional"))
      (node (ref "L61") (pin "1-VDD") (pinfunction "VDD_1-VDD") (pintype "bidirectional"))
      (node (ref "L62") (pin "1-VDD") (pinfunction "VDD_1-VDD") (pintype "bidirectional"))
      (node (ref "L63") (pin "1-VDD") (pinfunction "VDD_1-VDD") (pintype "bidirectional"))
      (node (ref "L64") (pin "1-VDD") (pinfunction "VDD_1-VDD") (pintype "bidirectional"))
      (node (ref "L65") (pin "1-VDD") (pinfunction "VDD_1-VDD") (pintype "bidirectional"))
      (node (ref "L66") (pin "1-VDD") (pinfunction "VDD_1-VDD") (pintype "bidirectional"))
      (node (ref "L67") (pin "1-VDD") (pinfunction "VDD_1-VDD") (pintype "bidirectional"))
      (node (ref "L68") (pin "1-VDD") (pinfunction "VDD_1-VDD") (pintype "bidirectional"))
      (node (ref "L69") (pin "1-VDD") (pinfunction "VDD_1-VDD") (pintype "bidirectional"))
      (node (ref "L7") (pin "1-VDD") (pinfunction "VDD_1-VDD") (pintype "bidirectional"))
      (node (ref "L70") (pin "1-VDD") (pinfunction "VDD_1-VDD") (pintype "bidirectional"))
      (node (ref "L71") (pin "1-VDD") (pinfunction "VDD_1-VDD") (pintype "bidirectional"))
      (node (ref "L72") (pin "1-VDD") (pinfunction "VDD_1-VDD") (pintype "bidirectional"))
      (node (ref "L73") (pin "1-VDD") (pinfunction "VDD_1-VDD") (pintype "bidirectional"))
      (node (ref "L74") (pin "1-VDD") (pinfunction "VDD_1-VDD") (pintype "bidirectional"))
      (node (ref "L75") (pin "1-VDD") (pinfunction "VDD_1-VDD") (pintype "bidirectional"))
      (node (ref "L76") (pin "1-VDD") (pinfunction "VDD_1-VDD") (pintype "bidirectional"))
      (node (ref "L77") (pin "1-VDD") (pinfunction "VDD_1-VDD") (pintype "bidirectional"))
      (node (ref "L78") (pin "1-VDD") (pinfunction "VDD_1-VDD") (pintype "bidirectional"))
      (node (ref "L79") (pin "1-VDD") (pinfunction "VDD_1-VDD") (pintype "bidirectional"))
      (node (ref "L8") (pin "1-VDD") (pinfunction "VDD_1-VDD") (pintype "bidirectional"))
      (node (ref "L80") (pin "1-VDD") (pinfunction "VDD_1-VDD") (pintype "bidirectional"))
      (node (ref "L81") (pin "1-VDD") (pinfunction "VDD_1-VDD") (pintype "bidirectional"))
      (node (ref "L82") (pin "1-VDD") (pinfunction "VDD_1-VDD") (pintype "bidirectional"))
      (node (ref "L83") (pin "1-VDD") (pinfunction "VDD_1-VDD") (pintype "bidirectional"))
      (node (ref "L84") (pin "1-VDD") (pinfunction "VDD_1-VDD") (pintype "bidirectional"))
      (node (ref "L85") (pin "1-VDD") (pinfunction "VDD_1-VDD") (pintype "bidirectional"))
      (node (ref "L86") (pin "1-VDD") (pinfunction "VDD_1-VDD") (pintype "bidirectional"))
      (node (ref "L87") (pin "1-VDD") (pinfunction "VDD_1-VDD") (pintype "bidirectional"))
      (node (ref "L88") (pin "1-VDD") (pinfunction "VDD_1-VDD") (pintype "bidirectional"))
      (node (ref "L89") (pin "1-VDD") (pinfunction "VDD_1-VDD") (pintype "bidirectional"))
      (node (ref "L9") (pin "1-VDD") (pinfunction "VDD_1-VDD") (pintype "bidirectional"))
      (node (ref "L90") (pin "1-VDD") (pinfunction "VDD_1-VDD") (pintype "bidirectional"))
      (node (ref "L91") (pin "1-VDD") (pinfunction "VDD_1-VDD") (pintype "bidirectional"))
      (node (ref "L92") (pin "1-VDD") (pinfunction "VDD_1-VDD") (pintype "bidirectional"))
      (node (ref "L93") (pin "1-VDD") (pinfunction "VDD_1-VDD") (pintype "bidirectional"))
      (node (ref "L94") (pin "1-VDD") (pinfunction "VDD_1-VDD") (pintype "bidirectional"))
      (node (ref "L95") (pin "1-VDD") (pinfunction "VDD_1-VDD") (pintype "bidirectional"))
      (node (ref "L96") (pin "1-VDD") (pinfunction "VDD_1-VDD") (pintype "bidirectional"))
      (node (ref "L97") (pin "1-VDD") (pinfunction "VDD_1-VDD") (pintype "bidirectional"))
      (node (ref "L98") (pin "1-VDD") (pinfunction "VDD_1-VDD") (pintype "bidirectional"))
      (node (ref "L99") (pin "1-VDD") (pinfunction "VDD_1-VDD") (pintype "bidirectional"))
    )
    (net (code "2") (name "GND") (class "Default")
      (node (ref "C1") (pin "2") (pinfunction "2_2") (pintype "passive"))
      (node (ref "C10") (pin "2") (pinfunction "2_2") (pintype "passive"))
      (node (ref "C100") (pin "2") (pinfunction "2_2") (pintype "passive"))
      (node (ref "C101") (pin "2") (pinfunction "2_2") (pintype "passive"))
      (node (ref "C102") (pin "2") (pinfunction "2_2") (pintype "passive"))
      (node (ref "C103") (pin "2") (pinfunction "2_2") (pintype "passive"))
      (node (ref "C104") (pin "2") (pinfunction "2_2") (pintype "passive"))
      (node (ref "C105") (pin "2") (pinfunction "2_2") (pintype "passive"))
      (node (ref "C106") (pin "2") (pinfunction "2_2") (pintype "passive"))
      (node (ref "C107") (pin "2") (pinfunction "2_2") (pintype "passive"))
      (node (ref "C108") (pin "2") (pinfunction "2_2") (pintype "passive"))
      (node (ref "C109") (pin "2") (pinfunction "2_2") (pintype "passive"))
      (node (ref "C11") (pin "2") (pinfunction "2_2") (pintype "passive"))
      (node (ref "C110") (pin "2") (pinfunction "2_2") (pintype "passive"))
      (node (ref "C12") (pin "2") (pinfunction "2_2") (pintype "passive"))
      (node (ref "C13") (pin "2") (pinfunction "2_2") (pintype "passive"))
      (node (ref "C14") (pin "2") (pinfunction "2_2") (pintype "passive"))
      (node (ref "C15") (pin "2") (pinfunction "2_2") (pintype "passive"))
      (node (ref "C16") (pin "2") (pinfunction "2_2") (pintype "passive"))
      (node (ref "C17") (pin "2") (pinfunction "2_2") (pintype "passive"))
      (node (ref "C18") (pin "2") (pinfunction "2_2") (pintype "passive"))
      (node (ref "C19") (pin "2") (pinfunction "2_2") (pintype "passive"))
      (node (ref "C2") (pin "2") (pinfunction "2_2") (pintype "passive"))
      (node (ref "C20") (pin "2") (pinfunction "2_2") (pintype "passive"))
      (node (ref "C21") (pin "2") (pinfunction "2_2") (pintype "passive"))
      (node (ref "C22") (pin "2") (pinfunction "2_2") (pintype "passive"))
      (node (ref "C23") (pin "2") (pinfunction "2_2") (pintype "passive"))
      (node (ref "C24") (pin "2") (pinfunction "2_2") (pintype "passive"))
      (node (ref "C25") (pin "2") (pinfunction "2_2") (pintype "passive"))
      (node (ref "C26") (pin "2") (pinfunction "2_2") (pintype "passive"))
      (node (ref "C27") (pin "2") (pinfunction "2_2") (pintype "passive"))
      (node (ref "C28") (pin "2") (pinfunction "2_2") (pintype "passive"))
      (node (ref "C29") (pin "2") (pinfunction "2_2") (pintype "passive"))
      (node (ref "C3") (pin "2") (pinfunction "2_2") (pintype "passive"))
      (node (ref "C30") (pin "2") (pinfunction "2_2") (pintype "passive"))
      (node (ref "C31") (pin "2") (pinfunction "2_2") (pintype "passive"))
      (node (ref "C32") (pin "2") (pinfunction "2_2") (pintype "passive"))
      (node (ref "C33") (pin "2") (pinfunction "2_2") (pintype "passive"))
      (node (ref "C34") (pin "2") (pinfunction "2_2") (pintype "passive"))
      (node (ref "C35") (pin "2") (pinfunction "2_2") (pintype "passive"))
      (node (ref "C36") (pin "2") (pinfunction "2_2") (pintype "passive"))
      (node (ref "C37") (pin "2") (pinfunction "2_2") (pintype "passive"))
      (node (ref "C38") (pin "2") (pinfunction "2_2") (pintype "passive"))
      (node (ref "C39") (pin "2") (pinfunction "2_2") (pintype "passive"))
      (node (ref "C4") (pin "2") (pinfunction "2_2") (pintype "passive"))
      (node (ref "C40") (pin "2") (pinfunction "2_2") (pintype "passive"))
      (node (ref "C41") (pin "2") (pinfunction "2_2") (pintype "passive"))
      (node (ref "C42") (pin "2") (pinfunction "2_2") (pintype "passive"))
      (node (ref "C43") (pin "2") (pinfunction "2_2") (pintype "passive"))
      (node (ref "C44") (pin "2") (pinfunction "2_2") (pintype "passive"))
      (node (ref "C45") (pin "2") (pinfunction "2_2") (pintype "passive"))
      (node (ref "C46") (pin "2") (pinfunction "2_2") (pintype "passive"))
      (node (ref "C47") (pin "2") (pinfunction "2_2") (pintype "passive"))
      (node (ref "C48") (pin "2") (pinfunction "2_2") (pintype "passive"))
      (node (ref "C49") (pin "2") (pinfunction "2_2") (pintype "passive"))
      (node (ref "C5") (pin "2") (pinfunction "2_2") (pintype "passive"))
      (node (ref "C50") (pin "2") (pinfunction "2_2") (pintype "passive"))
      (node (ref "C51") (pin "2") (pinfunction "2_2") (pintype "passive"))
      (node (ref "C52") (pin "2") (pinfunction "2_2") (pintype "passive"))
      (node (ref "C53") (pin "2") (pinfunction "2_2") (pintype "passive"))
      (node (ref "C54") (pin "2") (pinfunction "2_2") (pintype "passive"))
      (node (ref "C55") (pin "2") (pinfunction "2_2") (pintype "passive"))
      (node (ref "C56") (pin "2") (pinfunction "2_2") (pintype "passive"))
      (node (ref "C57") (pin "2") (pinfunction "2_2") (pintype "passive"))
      (node (ref "C58") (pin "2") (pinfunction "2_2") (pintype "passive"))
      (node (ref "C59") (pin "2") (pinfunction "2_2") (pintype "passive"))
      (node (ref "C6") (pin "2") (pinfunction "2_2") (pintype "passive"))
      (node (ref "C60") (pin "2") (pinfunction "2_2") (pintype "passive"))
      (node (ref "C61") (pin "2") (pinfunction "2_2") (pintype "passive"))
      (node (ref "C62") (pin "2") (pinfunction "2_2") (pintype "passive"))
      (node (ref "C63") (pin "2") (pinfunction "2_2") (pintype "passive"))
      (node (ref "C64") (pin "2") (pinfunction "2_2") (pintype "passive"))
      (node (ref "C65") (pin "2") (pinfunction "2_2") (pintype "passive"))
      (node (ref "C66") (pin "2") (pinfunction "2_2") (pintype "passive"))
      (node (ref "C67") (pin "2") (pinfunction "2_2") (pintype "passive"))
      (node (ref "C68") (pin "2") (pinfunction "2_2") (pintype "passive"))
      (node (ref "C69") (pin "2") (pinfunction "2_2") (pintype "passive"))
      (node (ref "C7") (pin "2") (pinfunction "2_2") (pintype "passive"))
      (node (ref "C70") (pin "2") (pinfunction "2_2") (pintype "passive"))
      (node (ref "C71") (pin "2") (pinfunction "2_2") (pintype "passive"))
      (node (ref "C72") (pin "2") (pinfunction "2_2") (pintype "passive"))
      (node (ref "C73") (pin "2") (pinfunction "2_2") (pintype "passive"))
      (node (ref "C74") (pin "2") (pinfunction "2_2") (pintype "passive"))
      (node (ref "C75") (pin "2") (pinfunction "2_2") (pintype "passive"))
      (node (ref "C76") (pin "2") (pinfunction "2_2") (pintype "passive"))
      (node (ref "C77") (pin "2") (pinfunction "2_2") (pintype "passive"))
      (node (ref "C78") (pin "2") (pinfunction "2_2") (pintype "passive"))
      (node (ref "C79") (pin "2") (pinfunction "2_2") (pintype "passive"))
      (node (ref "C8") (pin "2") (pinfunction "2_2") (pintype "passive"))
      (node (ref "C80") (pin "2") (pinfunction "2_2") (pintype "passive"))
      (node (ref "C81") (pin "2") (pinfunction "2_2") (pintype "passive"))
      (node (ref "C82") (pin "2") (pinfunction "2_2") (pintype "passive"))
      (node (ref "C83") (pin "2") (pinfunction "2_2") (pintype "passive"))
      (node (ref "C84") (pin "2") (pinfunction "2_2") (pintype "passive"))
      (node (ref "C85") (pin "2") (pinfunction "2_2") (pintype "passive"))
      (node (ref "C86") (pin "2") (pinfunction "2_2") (pintype "passive"))
      (node (ref "C87") (pin "2") (pinfunction "2_2") (pintype "passive"))
      (node (ref "C88") (pin "2") (pinfunction "2_2") (pintype "passive"))
      (node (ref "C89") (pin "2") (pinfunction "2_2") (pintype "passive"))
      (node (ref "C9") (pin "2") (pinfunction "2_2") (pintype "passive"))
      (node (ref "C90") (pin "2") (pinfunction "2_2") (pintype "passive"))
      (node (ref "C91") (pin "2") (pinfunction "2_2") (pintype "passive"))
      (node (ref "C92") (pin "2") (pinfunction "2_2") (pintype "passive"))
      (node (ref "C93") (pin "2") (pinfunction "2_2") (pintype "passive"))
      (node (ref "C94") (pin "2") (pinfunction "2_2") (pintype "passive"))
      (node (ref "C95") (pin "2") (pinfunction "2_2") (pintype "passive"))
      (node (ref "C96") (pin "2") (pinfunction "2_2") (pintype "passive"))
      (node (ref "C97") (pin "2") (pinfunction "2_2") (pintype "passive"))
      (node (ref "C98") (pin "2") (pinfunction "2_2") (pintype "passive"))
      (node (ref "C99") (pin "2") (pinfunction "2_2") (pintype "passive"))
      (node (ref "L1") (pin "3-GND") (pinfunction "GND_3-GND") (pintype "bidirectional"))
      (node (ref "L10") (pin "3-GND") (pinfunction "GND_3-GND") (pintype "bidirectional"))
      (node (ref "L100") (pin "3-GND") (pinfunction "GND_3-GND") (pintype "bidirectional"))
      (node (ref "L101") (pin "3-GND") (pinfunction "GND_3-GND") (pintype "bidirectional"))
      (node (ref "L102") (pin "3-GND") (pinfunction "GND_3-GND") (pintype "bidirectional"))
      (node (ref "L103") (pin "3-GND") (pinfunction "GND_3-GND") (pintype "bidirectional"))
      (node (ref "L104") (pin "3-GND") (pinfunction "GND_3-GND") (pintype "bidirectional"))
      (node (ref "L105") (pin "3-GND") (pinfunction "GND_3-GND") (pintype "bidirectional"))
      (node (ref "L106") (pin "3-GND") (pinfunction "GND_3-GND") (pintype "bidirectional"))
      (node (ref "L107") (pin "3-GND") (pinfunction "GND_3-GND") (pintype "bidirectional"))
      (node (ref "L108") (pin "3-GND") (pinfunction "GND_3-GND") (pintype "bidirectional"))
      (node (ref "L109") (pin "3-GND") (pinfunction "GND_3-GND") (pintype "bidirectional"))
      (node (ref "L11") (pin "3-GND") (pinfunction "GND_3-GND") (pintype "bidirectional"))
      (node (ref "L110") (pin "3-GND") (pinfunction "GND_3-GND") (pintype "bidirectional"))
      (node (ref "L12") (pin "3-GND") (pinfunction "GND_3-GND") (pintype "bidirectional"))
      (node (ref "L13") (pin "3-GND") (pinfunction "GND_3-GND") (pintype "bidirectional"))
      (node (ref "L14") (pin "3-GND") (pinfunction "GND_3-GND") (pintype "bidirectional"))
      (node (ref "L15") (pin "3-GND") (pinfunction "GND_3-GND") (pintype "bidirectional"))
      (node (ref "L16") (pin "3-GND") (pinfunction "GND_3-GND") (pintype "bidirectional"))
      (node (ref "L17") (pin "3-GND") (pinfunction "GND_3-GND") (pintype "bidirectional"))
      (node (ref "L18") (pin "3-GND") (pinfunction "GND_3-GND") (pintype "bidirectional"))
      (node (ref "L19") (pin "3-GND") (pinfunction "GND_3-GND") (pintype "bidirectional"))
      (node (ref "L2") (pin "3-GND") (pinfunction "GND_3-GND") (pintype "bidirectional"))
      (node (ref "L20") (pin "3-GND") (pinfunction "GND_3-GND") (pintype "bidirectional"))
      (node (ref "L21") (pin "3-GND") (pinfunction "GND_3-GND") (pintype "bidirectional"))
      (node (ref "L22") (pin "3-GND") (pinfunction "GND_3-GND") (pintype "bidirectional"))
      (node (ref "L23") (pin "3-GND") (pinfunction "GND_3-GND") (pintype "bidirectional"))
      (node (ref "L24") (pin "3-GND") (pinfunction "GND_3-GND") (pintype "bidirectional"))
      (node (ref "L25") (pin "3-GND") (pinfunction "GND_3-GND") (pintype "bidirectional"))
      (node (ref "L26") (pin "3-GND") (pinfunction "GND_3-GND") (pintype "bidirectional"))
      (node (ref "L27") (pin "3-GND") (pinfunction "GND_3-GND") (pintype "bidirectional"))
      (node (ref "L28") (pin "3-GND") (pinfunction "GND_3-GND") (pintype "bidirectional"))
      (node (ref "L29") (pin "3-GND") (pinfunction "GND_3-GND") (pintype "bidirectional"))
      (node (ref "L3") (pin "3-GND") (pinfunction "GND_3-GND") (pintype "bidirectional"))
      (node (ref "L30") (pin "3-GND") (pinfunction "GND_3-GND") (pintype "bidirectional"))
      (node (ref "L31") (pin "3-GND") (pinfunction "GND_3-GND") (pintype "bidirectional"))
      (node (ref "L32") (pin "3-GND") (pinfunction "GND_3-GND") (pintype "bidirectional"))
      (node (ref "L33") (pin "3-GND") (pinfunction "GND_3-GND") (pintype "bidirectional"))
      (node (ref "L34") (pin "3-GND") (pinfunction "GND_3-GND") (pintype "bidirectional"))
      (node (ref "L35") (pin "3-GND") (pinfunction "GND_3-GND") (pintype "bidirectional"))
      (node (ref "L36") (pin "3-GND") (pinfunction "GND_3-GND") (pintype "bidirectional"))
      (node (ref "L37") (pin "3-GND") (pinfunction "GND_3-GND") (pintype "bidirectional"))
      (node (ref "L38") (pin "3-GND") (pinfunction "GND_3-GND") (pintype "bidirectional"))
      (node (ref "L39") (pin "3-GND") (pinfunction "GND_3-GND") (pintype "bidirectional"))
      (node (ref "L4") (pin "3-GND") (pinfunction "GND_3-GND") (pintype "bidirectional"))
      (node (ref "L40") (pin "3-GND") (pinfunction "GND_3-GND") (pintype "bidirectional"))
      (node (ref "L41") (pin "3-GND") (pinfunction "GND_3-GND") (pintype "bidirectional"))
      (node (ref "L42") (pin "3-GND") (pinfunction "GND_3-GND") (pintype "bidirectional"))
      (node (ref "L43") (pin "3-GND") (pinfunction "GND_3-GND") (pintype "bidirectional"))
      (node (ref "L44") (pin "3-GND") (pinfunction "GND_3-GND") (pintype "bidirectional"))
      (node (ref "L45") (pin "3-GND") (pinfunction "GND_3-GND") (pintype "bidirectional"))
      (node (ref "L46") (pin "3-GND") (pinfunction "GND_3-GND") (pintype "bidirectional"))
      (node (ref "L47") (pin "3-GND") (pinfunction "GND_3-GND") (pintype "bidirectional"))
      (node (ref "L48") (pin "3-GND") (pinfunction "GND_3-GND") (pintype "bidirectional"))
      (node (ref "L49") (pin "3-GND") (pinfunction "GND_3-GND") (pintype "bidirectional"))
      (node (ref "L5") (pin "3-GND") (pinfunction "GND_3-GND") (pintype "bidirectional"))
      (node (ref "L50") (pin "3-GND") (pinfunction "GND_3-GND") (pintype "bidirectional"))
      (node (ref "L51") (pin "3-GND") (pinfunction "GND_3-GND") (pintype "bidirectional"))
      (node (ref "L52") (pin "3-GND") (pinfunction "GND_3-GND") (pintype "bidirectional"))
      (node (ref "L53") (pin "3-GND") (pinfunction "GND_3-GND") (pintype "bidirectional"))
      (node (ref "L54") (pin "3-GND") (pinfunction "GND_3-GND") (pintype "bidirectional"))
      (node (ref "L55") (pin "3-GND") (pinfunction "GND_3-GND") (pintype "bidirectional"))
      (node (ref "L56") (pin "3-GND") (pinfunction "GND_3-GND") (pintype "bidirectional"))
      (node (ref "L57") (pin "3-GND") (pinfunction "GND_3-GND") (pintype "bidirectional"))
      (node (ref "L58") (pin "3-GND") (pinfunction "GND_3-GND") (pintype "bidirectional"))
      (node (ref "L59") (pin "3-GND") (pinfunction "GND_3-GND") (pintype "bidirectional"))
      (node (ref "L6") (pin "3-GND") (pinfunction "GND_3-GND") (pintype "bidirectional"))
      (node (ref "L60") (pin "3-GND") (pinfunction "GND_3-GND") (pintype "bidirectional"))
      (node (ref "L61") (pin "3-GND") (pinfunction "GND_3-GND") (pintype "bidirectional"))
      (node (ref "L62") (pin "3-GND") (pinfunction "GND_3-GND") (pintype "bidirectional"))
      (node (ref "L63") (pin "3-GND") (pinfunction "GND_3-GND") (pintype "bidirectional"))
      (node (ref "L64") (pin "3-GND") (pinfunction "GND_3-GND") (pintype "bidirectional"))
      (node (ref "L65") (pin "3-GND") (pinfunction "GND_3-GND") (pintype "bidirectional"))
      (node (ref "L66") (pin "3-GND") (pinfunction "GND_3-GND") (pintype "bidirectional"))
      (node (ref "L67") (pin "3-GND") (pinfunction "GND_3-GND") (pintype "bidirectional"))
      (node (ref "L68") (pin "3-GND") (pinfunction "GND_3-GND") (pintype "bidirectional"))
      (node (ref "L69") (pin "3-GND") (pinfunction "GND_3-GND") (pintype "bidirectional"))
      (node (ref "L7") (pin "3-GND") (pinfunction "GND_3-GND") (pintype "bidirectional"))
      (node (ref "L70") (pin "3-GND") (pinfunction "GND_3-GND") (pintype "bidirectional"))
      (node (ref "L71") (pin "3-GND") (pinfunction "GND_3-GND") (pintype "bidirectional"))
      (node (ref "L72") (pin "3-GND") (pinfunction "GND_3-GND") (pintype "bidirectional"))
      (node (ref "L73") (pin "3-GND") (pinfunction "GND_3-GND") (pintype "bidirectional"))
      (node (ref "L74") (pin "3-GND") (pinfunction "GND_3-GND") (pintype "bidirectional"))
      (node (ref "L75") (pin "3-GND") (pinfunction "GND_3-GND") (pintype "bidirectional"))
      (node (ref "L76") (pin "3-GND") (pinfunction "GND_3-GND") (pintype "bidirectional"))
      (node (ref "L77") (pin "3-GND") (pinfunction "GND_3-GND") (pintype "bidirectional"))
      (node (ref "L78") (pin "3-GND") (pinfunction "GND_3-GND") (pintype "bidirectional"))
      (node (ref "L79") (pin "3-GND") (pinfunction "GND_3-GND") (pintype "bidirectional"))
      (node (ref "L8") (pin "3-GND") (pinfunction "GND_3-GND") (pintype "bidirectional"))
      (node (ref "L80") (pin "3-GND") (pinfunction "GND_3-GND") (pintype "bidirectional"))
      (node (ref "L81") (pin "3-GND") (pinfunction "GND_3-GND") (pintype "bidirectional"))
      (node (ref "L82") (pin "3-GND") (pinfunction "GND_3-GND") (pintype "bidirectional"))
      (node (ref "L83") (pin "3-GND") (pinfunction "GND_3-GND") (pintype "bidirectional"))
      (node (ref "L84") (pin "3-GND") (pinfunction "GND_3-GND") (pintype "bidirectional"))
      (node (ref "L85") (pin "3-GND") (pinfunction "GND_3-GND") (pintype "bidirectional"))
      (node (ref "L86") (pin "3-GND") (pinfunction "GND_3-GND") (pintype "bidirectional"))
      (node (ref "L87") (pin "3-GND") (pinfunction "GND_3-GND") (pintype "bidirectional"))
      (node (ref "L88") (pin "3-GND") (pinfunction "GND_3-GND") (pintype "bidirectional"))
      (node (ref "L89") (pin "3-GND") (pinfunction "GND_3-GND") (pintype "bidirectional"))
      (node (ref "L9") (pin "3-GND") (pinfunction "GND_3-GND") (pintype "bidirectional"))
      (node (ref "L90") (pin "3-GND") (pinfunction "GND_3-GND") (pintype "bidirectional"))
      (node (ref "L91") (pin "3-GND") (pinfunction "GND_3-GND") (pintype "bidirectional"))
      (node (ref "L92") (pin "3-GND") (pinfunction "GND_3-GND") (pintype "bidirectional"))
      (node (ref "L93") (pin "3-GND") (pinfunction "GND_3-GND") (pintype "bidirectional"))
      (node (ref "L94") (pin "3-GND") (pinfunction "GND_3-GND") (pintype "bidirectional"))
      (node (ref "L95") (pin "3-GND") (pinfunction "GND_3-GND") (pintype "bidirectional"))
      (node (ref "L96") (pin "3-GND") (pinfunction "GND_3-GND") (pintype "bidirectional"))
      (node (ref "L97") (pin "3-GND") (pinfunction "GND_3-GND") (pintype "bidirectional"))
      (node (ref "L98") (pin "3-GND") (pinfunction "GND_3-GND") (pintype "bidirectional"))
      (node (ref "L99") (pin "3-GND") (pinfunction "GND_3-GND") (pintype "bidirectional"))
      (node (ref "S+1") (pin "4") (pinfunction "GND_4") (pintype "bidirectional"))
      (node (ref "U$1") (pin "5") (pinfunction "5_5") (pintype "input"))
    )
    (net (code "3") (name "Net-(L1-DOUT)") (class "Default")
      (node (ref "L1") (pin "2-DOUT") (pinfunction "DOUT_2-DOUT") (pintype "output"))
      (node (ref "L2") (pin "4-DIN") (pinfunction "DIN_4-DIN") (pintype "input"))
    )
    (net (code "4") (name "Net-(L2-DOUT)") (class "Default")
      (node (ref "L2") (pin "2-DOUT") (pinfunction "DOUT_2-DOUT") (pintype "output"))
      (node (ref "L3") (pin "4-DIN") (pinfunction "DIN_4-DIN") (pintype "input"))
    )
    (net (code "5") (name "Net-(L3-DOUT)") (class "Default")
      (node (ref "L3") (pin "2-DOUT") (pinfunction "DOUT_2-DOUT") (pintype "output"))
      (node (ref "L4") (pin "4-DIN") (pinfunction "DIN_4-DIN") (pintype "input"))
    )
    (net (code "6") (name "Net-(L4-DOUT)") (class "Default")
      (node (ref "L4") (pin "2-DOUT") (pinfunction "DOUT_2-DOUT") (pintype "output"))
      (node (ref "L5") (pin "4-DIN") (pinfunction "DIN_4-DIN") (pintype "input"))
    )
    (net (code "7") (name "Net-(L5-DOUT)") (class "Default")
      (node (ref "L5") (pin "2-DOUT") (pinfunction "DOUT_2-DOUT") (pintype "output"))
      (node (ref "L6") (pin "4-DIN") (pinfunction "DIN_4-DIN") (pintype "input"))
    )
    (net (code "8") (name "Net-(L6-DOUT)") (class "Default")
      (node (ref "L6") (pin "2-DOUT") (pinfunction "DOUT_2-DOUT") (pintype "output"))
      (node (ref "L7") (pin "4-DIN") (pinfunction "DIN_4-DIN") (pintype "input"))
    )
    (net (code "9") (name "Net-(L7-DOUT)") (class "Default")
      (node (ref "L7") (pin "2-DOUT") (pinfunction "DOUT_2-DOUT") (pintype "output"))
      (node (ref "L8") (pin "4-DIN") (pinfunction "DIN_4-DIN") (pintype "input"))
    )
    (net (code "10") (name "Net-(L8-DOUT)") (class "Default")
      (node (ref "L8") (pin "2-DOUT") (pinfunction "DOUT_2-DOUT") (pintype "output"))
      (node (ref "L9") (pin "4-DIN") (pinfunction "DIN_4-DIN") (pintype "input"))
    )
    (net (code "11") (name "Net-(L10-DIN)") (class "Default")
      (node (ref "L10") (pin "4-DIN") (pinfunction "DIN_4-DIN") (pintype "input"))
      (node (ref "L9") (pin "2-DOUT") (pinfunction "DOUT_2-DOUT") (pintype "output"))
    )
    (net (code "12") (name "Net-(L10-DOUT)") (class "Default")
      (node (ref "L10") (pin "2-DOUT") (pinfunction "DOUT_2-DOUT") (pintype "output"))
      (node (ref "L11") (pin "4-DIN") (pinfunction "DIN_4-DIN") (pintype "input"))
    )
    (net (code "13") (name "Net-(L12-DOUT)") (class "Default")
      (node (ref "L12") (pin "2-DOUT") (pinfunction "DOUT_2-DOUT") (pintype "output"))
      (node (ref "L13") (pin "4-DIN") (pinfunction "DIN_4-DIN") (pintype "input"))
    )
    (net (code "14") (name "Net-(L13-DOUT)") (class "Default")
      (node (ref "L13") (pin "2-DOUT") (pinfunction "DOUT_2-DOUT") (pintype "output"))
      (node (ref "L14") (pin "4-DIN") (pinfunction "DIN_4-DIN") (pintype "input"))
    )
    (net (code "15") (name "Net-(L14-DOUT)") (class "Default")
      (node (ref "L14") (pin "2-DOUT") (pinfunction "DOUT_2-DOUT") (pintype "output"))
      (node (ref "L15") (pin "4-DIN") (pinfunction "DIN_4-DIN") (pintype "input"))
    )
    (net (code "16") (name "Net-(L15-DOUT)") (class "Default")
      (node (ref "L15") (pin "2-DOUT") (pinfunction "DOUT_2-DOUT") (pintype "output"))
      (node (ref "L16") (pin "4-DIN") (pinfunction "DIN_4-DIN") (pintype "input"))
    )
    (net (code "17") (name "Net-(L16-DOUT)") (class "Default")
      (node (ref "L16") (pin "2-DOUT") (pinfunction "DOUT_2-DOUT") (pintype "output"))
      (node (ref "L17") (pin "4-DIN") (pinfunction "DIN_4-DIN") (pintype "input"))
    )
    (net (code "18") (name "Net-(L17-DOUT)") (class "Default")
      (node (ref "L17") (pin "2-DOUT") (pinfunction "DOUT_2-DOUT") (pintype "output"))
      (node (ref "L18") (pin "4-DIN") (pinfunction "DIN_4-DIN") (pintype "input"))
    )
    (net (code "19") (name "Net-(L18-DOUT)") (class "Default")
      (node (ref "L18") (pin "2-DOUT") (pinfunction "DOUT_2-DOUT") (pintype "output"))
      (node (ref "L19") (pin "4-DIN") (pinfunction "DIN_4-DIN") (pintype "input"))
    )
    (net (code "20") (name "Net-(L19-DOUT)") (class "Default")
      (node (ref "L19") (pin "2-DOUT") (pinfunction "DOUT_2-DOUT") (pintype "output"))
      (node (ref "L20") (pin "4-DIN") (pinfunction "DIN_4-DIN") (pintype "input"))
    )
    (net (code "21") (name "Net-(L20-DOUT)") (class "Default")
      (node (ref "L20") (pin "2-DOUT") (pinfunction "DOUT_2-DOUT") (pintype "output"))
      (node (ref "L21") (pin "4-DIN") (pinfunction "DIN_4-DIN") (pintype "input"))
    )
    (net (code "22") (name "Net-(L21-DOUT)") (class "Default")
      (node (ref "L21") (pin "2-DOUT") (pinfunction "DOUT_2-DOUT") (pintype "output"))
      (node (ref "L22") (pin "4-DIN") (pinfunction "DIN_4-DIN") (pintype "input"))
    )
    (net (code "23") (name "Net-(L23-DOUT)") (class "Default")
      (node (ref "L23") (pin "2-DOUT") (pinfunction "DOUT_2-DOUT") (pintype "output"))
      (node (ref "L24") (pin "4-DIN") (pinfunction "DIN_4-DIN") (pintype "input"))
    )
    (net (code "24") (name "Net-(L24-DOUT)") (class "Default")
      (node (ref "L24") (pin "2-DOUT") (pinfunction "DOUT_2-DOUT") (pintype "output"))
      (node (ref "L25") (pin "4-DIN") (pinfunction "DIN_4-DIN") (pintype "input"))
    )
    (net (code "25") (name "Net-(L25-DOUT)") (class "Default")
      (node (ref "L25") (pin "2-DOUT") (pinfunction "DOUT_2-DOUT") (pintype "output"))
      (node (ref "L26") (pin "4-DIN") (pinfunction "DIN_4-DIN") (pintype "input"))
    )
    (net (code "26") (name "Net-(L26-DOUT)") (class "Default")
      (node (ref "L26") (pin "2-DOUT") (pinfunction "DOUT_2-DOUT") (pintype "output"))
      (node (ref "L27") (pin "4-DIN") (pinfunction "DIN_4-DIN") (pintype "input"))
    )
    (net (code "27") (name "Net-(L27-DOUT)") (class "Default")
      (node (ref "L27") (pin "2-DOUT") (pinfunction "DOUT_2-DOUT") (pintype "output"))
      (node (ref "L28") (pin "4-DIN") (pinfunction "DIN_4-DIN") (pintype "input"))
    )
    (net (code "28") (name "Net-(L28-DOUT)") (class "Default")
      (node (ref "L28") (pin "2-DOUT") (pinfunction "DOUT_2-DOUT") (pintype "output"))
      (node (ref "L29") (pin "4-DIN") (pinfunction "DIN_4-DIN") (pintype "input"))
    )
    (net (code "29") (name "Net-(L29-DOUT)") (class "Default")
      (node (ref "L29") (pin "2-DOUT") (pinfunction "DOUT_2-DOUT") (pintype "output"))
      (node (ref "L30") (pin "4-DIN") (pinfunction "DIN_4-DIN") (pintype "input"))
    )
    (net (code "30") (name "Net-(L30-DOUT)") (class "Default")
      (node (ref "L30") (pin "2-DOUT") (pinfunction "DOUT_2-DOUT") (pintype "output"))
      (node (ref "L31") (pin "4-DIN") (pinfunction "DIN_4-DIN") (pintype "input"))
    )
    (net (code "31") (name "Net-(L31-DOUT)") (class "Default")
      (node (ref "L31") (pin "2-DOUT") (pinfunction "DOUT_2-DOUT") (pintype "output"))
      (node (ref "L32") (pin "4-DIN") (pinfunction "DIN_4-DIN") (pintype "input"))
    )
    (net (code "32") (name "Net-(L32-DOUT)") (class "Default")
      (node (ref "L32") (pin "2-DOUT") (pinfunction "DOUT_2-DOUT") (pintype "output"))
      (node (ref "L33") (pin "4-DIN") (pinfunction "DIN_4-DIN") (pintype "input"))
    )
    (net (code "33") (name "Net-(L34-DOUT)") (class "Default")
      (node (ref "L34") (pin "2-DOUT") (pinfunction "DOUT_2-DOUT") (pintype "output"))
      (node (ref "L35") (pin "4-DIN") (pinfunction "DIN_4-DIN") (pintype "input"))
    )
    (net (code "34") (name "Net-(L35-DOUT)") (class "Default")
      (node (ref "L35") (pin "2-DOUT") (pinfunction "DOUT_2-DOUT") (pintype "output"))
      (node (ref "L36") (pin "4-DIN") (pinfunction "DIN_4-DIN") (pintype "input"))
    )
    (net (code "35") (name "Net-(L36-DOUT)") (class "Default")
      (node (ref "L36") (pin "2-DOUT") (pinfunction "DOUT_2-DOUT") (pintype "output"))
      (node (ref "L37") (pin "4-DIN") (pinfunction "DIN_4-DIN") (pintype "input"))
    )
    (net (code "36") (name "Net-(L37-DOUT)") (class "Default")
      (node (ref "L37") (pin "2-DOUT") (pinfunction "DOUT_2-DOUT") (pintype "output"))
      (node (ref "L38") (pin "4-DIN") (pinfunction "DIN_4-DIN") (pintype "input"))
    )
    (net (code "37") (name "Net-(L38-DOUT)") (class "Default")
      (node (ref "L38") (pin "2-DOUT") (pinfunction "DOUT_2-DOUT") (pintype "output"))
      (node (ref "L39") (pin "4-DIN") (pinfunction "DIN_4-DIN") (pintype "input"))
    )
    (net (code "38") (name "Net-(L39-DOUT)") (class "Default")
      (node (ref "L39") (pin "2-DOUT") (pinfunction "DOUT_2-DOUT") (pintype "output"))
      (node (ref "L40") (pin "4-DIN") (pinfunction "DIN_4-DIN") (pintype "input"))
    )
    (net (code "39") (name "Net-(L40-DOUT)") (class "Default")
      (node (ref "L40") (pin "2-DOUT") (pinfunction "DOUT_2-DOUT") (pintype "output"))
      (node (ref "L41") (pin "4-DIN") (pinfunction "DIN_4-DIN") (pintype "input"))
    )
    (net (code "40") (name "Net-(L41-DOUT)") (class "Default")
      (node (ref "L41") (pin "2-DOUT") (pinfunction "DOUT_2-DOUT") (pintype "output"))
      (node (ref "L42") (pin "4-DIN") (pinfunction "DIN_4-DIN") (pintype "input"))
    )
    (net (code "41") (name "Net-(L42-DOUT)") (class "Default")
      (node (ref "L42") (pin "2-DOUT") (pinfunction "DOUT_2-DOUT") (pintype "output"))
      (node (ref "L43") (pin "4-DIN") (pinfunction "DIN_4-DIN") (pintype "input"))
    )
    (net (code "42") (name "Net-(L43-DOUT)") (class "Default")
      (node (ref "L43") (pin "2-DOUT") (pinfunction "DOUT_2-DOUT") (pintype "output"))
      (node (ref "L44") (pin "4-DIN") (pinfunction "DIN_4-DIN") (pintype "input"))
    )
    (net (code "43") (name "Net-(L45-DOUT)") (class "Default")
      (node (ref "L45") (pin "2-DOUT") (pinfunction "DOUT_2-DOUT") (pintype "output"))
      (node (ref "L46") (pin "4-DIN") (pinfunction "DIN_4-DIN") (pintype "input"))
    )
    (net (code "44") (name "Net-(L46-DOUT)") (class "Default")
      (node (ref "L46") (pin "2-DOUT") (pinfunction "DOUT_2-DOUT") (pintype "output"))
      (node (ref "L47") (pin "4-DIN") (pinfunction "DIN_4-DIN") (pintype "input"))
    )
    (net (code "45") (name "Net-(L47-DOUT)") (class "Default")
      (node (ref "L47") (pin "2-DOUT") (pinfunction "DOUT_2-DOUT") (pintype "output"))
      (node (ref "L48") (pin "4-DIN") (pinfunction "DIN_4-DIN") (pintype "input"))
    )
    (net (code "46") (name "Net-(L48-DOUT)") (class "Default")
      (node (ref "L48") (pin "2-DOUT") (pinfunction "DOUT_2-DOUT") (pintype "output"))
      (node (ref "L49") (pin "4-DIN") (pinfunction "DIN_4-DIN") (pintype "input"))
    )
    (net (code "47") (name "Net-(L49-DOUT)") (class "Default")
      (node (ref "L49") (pin "2-DOUT") (pinfunction "DOUT_2-DOUT") (pintype "output"))
      (node (ref "L50") (pin "4-DIN") (pinfunction "DIN_4-DIN") (pintype "input"))
    )
    (net (code "48") (name "Net-(L50-DOUT)") (class "Default")
      (node (ref "L50") (pin "2-DOUT") (pinfunction "DOUT_2-DOUT") (pintype "output"))
      (node (ref "L51") (pin "4-DIN") (pinfunction "DIN_4-DIN") (pintype "input"))
    )
    (net (code "49") (name "Net-(L51-DOUT)") (class "Default")
      (node (ref "L51") (pin "2-DOUT") (pinfunction "DOUT_2-DOUT") (pintype "output"))
      (node (ref "L52") (pin "4-DIN") (pinfunction "DIN_4-DIN") (pintype "input"))
    )
    (net (code "50") (name "Net-(L52-DOUT)") (class "Default")
      (node (ref "L52") (pin "2-DOUT") (pinfunction "DOUT_2-DOUT") (pintype "output"))
      (node (ref "L53") (pin "4-DIN") (pinfunction "DIN_4-DIN") (pintype "input"))
    )
    (net (code "51") (name "Net-(L53-DOUT)") (class "Default")
      (node (ref "L53") (pin "2-DOUT") (pinfunction "DOUT_2-DOUT") (pintype "output"))
      (node (ref "L54") (pin "4-DIN") (pinfunction "DIN_4-DIN") (pintype "input"))
    )
    (net (code "52") (name "Net-(L54-DOUT)") (class "Default")
      (node (ref "L54") (pin "2-DOUT") (pinfunction "DOUT_2-DOUT") (pintype "output"))
      (node (ref "L55") (pin "4-DIN") (pinfunction "DIN_4-DIN") (pintype "input"))
    )
    (net (code "53") (name "Net-(L56-DOUT)") (class "Default")
      (node (ref "L56") (pin "2-DOUT") (pinfunction "DOUT_2-DOUT") (pintype "output"))
      (node (ref "L57") (pin "4-DIN") (pinfunction "DIN_4-DIN") (pintype "input"))
    )
    (net (code "54") (name "Net-(L57-DOUT)") (class "Default")
      (node (ref "L57") (pin "2-DOUT") (pinfunction "DOUT_2-DOUT") (pintype "output"))
      (node (ref "L58") (pin "4-DIN") (pinfunction "DIN_4-DIN") (pintype "input"))
    )
    (net (code "55") (name "Net-(L58-DOUT)") (class "Default")
      (node (ref "L58") (pin "2-DOUT") (pinfunction "DOUT_2-DOUT") (pintype "output"))
      (node (ref "L59") (pin "4-DIN") (pinfunction "DIN_4-DIN") (pintype "input"))
    )
    (net (code "56") (name "Net-(L59-DOUT)") (class "Default")
      (node (ref "L59") (pin "2-DOUT") (pinfunction "DOUT_2-DOUT") (pintype "output"))
      (node (ref "L60") (pin "4-DIN") (pinfunction "DIN_4-DIN") (pintype "input"))
    )
    (net (code "57") (name "Net-(L60-DOUT)") (class "Default")
      (node (ref "L60") (pin "2-DOUT") (pinfunction "DOUT_2-DOUT") (pintype "output"))
      (node (ref "L61") (pin "4-DIN") (pinfunction "DIN_4-DIN") (pintype "input"))
    )
    (net (code "58") (name "Net-(L61-DOUT)") (class "Default")
      (node (ref "L61") (pin "2-DOUT") (pinfunction "DOUT_2-DOUT") (pintype "output"))
      (node (ref "L62") (pin "4-DIN") (pinfunction "DIN_4-DIN") (pintype "input"))
    )
    (net (code "59") (name "Net-(L62-DOUT)") (class "Default")
      (node (ref "L62") (pin "2-DOUT") (pinfunction "DOUT_2-DOUT") (pintype "output"))
      (node (ref "L63") (pin "4-DIN") (pinfunction "DIN_4-DIN") (pintype "input"))
    )
    (net (code "60") (name "Net-(L63-DOUT)") (class "Default")
      (node (ref "L63") (pin "2-DOUT") (pinfunction "DOUT_2-DOUT") (pintype "output"))
      (node (ref "L64") (pin "4-DIN") (pinfunction "DIN_4-DIN") (pintype "input"))
    )
    (net (code "61") (name "Net-(L64-DOUT)") (class "Default")
      (node (ref "L64") (pin "2-DOUT") (pinfunction "DOUT_2-DOUT") (pintype "output"))
      (node (ref "L65") (pin "4-DIN") (pinfunction "DIN_4-DIN") (pintype "input"))
    )
    (net (code "62") (name "Net-(L65-DOUT)") (class "Default")
      (node (ref "L65") (pin "2-DOUT") (pinfunction "DOUT_2-DOUT") (pintype "output"))
      (node (ref "L66") (pin "4-DIN") (pinfunction "DIN_4-DIN") (pintype "input"))
    )
    (net (code "63") (name "Net-(L67-DOUT)") (class "Default")
      (node (ref "L67") (pin "2-DOUT") (pinfunction "DOUT_2-DOUT") (pintype "output"))
      (node (ref "L68") (pin "4-DIN") (pinfunction "DIN_4-DIN") (pintype "input"))
    )
    (net (code "64") (name "Net-(L68-DOUT)") (class "Default")
      (node (ref "L68") (pin "2-DOUT") (pinfunction "DOUT_2-DOUT") (pintype "output"))
      (node (ref "L69") (pin "4-DIN") (pinfunction "DIN_4-DIN") (pintype "input"))
    )
    (net (code "65") (name "Net-(L69-DOUT)") (class "Default")
      (node (ref "L69") (pin "2-DOUT") (pinfunction "DOUT_2-DOUT") (pintype "output"))
      (node (ref "L70") (pin "4-DIN") (pinfunction "DIN_4-DIN") (pintype "input"))
    )
    (net (code "66") (name "Net-(L70-DOUT)") (class "Default")
      (node (ref "L70") (pin "2-DOUT") (pinfunction "DOUT_2-DOUT") (pintype "output"))
      (node (ref "L71") (pin "4-DIN") (pinfunction "DIN_4-DIN") (pintype "input"))
    )
    (net (code "67") (name "Net-(L71-DOUT)") (class "Default")
      (node (ref "L71") (pin "2-DOUT") (pinfunction "DOUT_2-DOUT") (pintype "output"))
      (node (ref "L72") (pin "4-DIN") (pinfunction "DIN_4-DIN") (pintype "input"))
    )
    (net (code "68") (name "Net-(L72-DOUT)") (class "Default")
      (node (ref "L72") (pin "2-DOUT") (pinfunction "DOUT_2-DOUT") (pintype "output"))
      (node (ref "L73") (pin "4-DIN") (pinfunction "DIN_4-DIN") (pintype "input"))
    )
    (net (code "69") (name "Net-(L73-DOUT)") (class "Default")
      (node (ref "L73") (pin "2-DOUT") (pinfunction "DOUT_2-DOUT") (pintype "output"))
      (node (ref "L74") (pin "4-DIN") (pinfunction "DIN_4-DIN") (pintype "input"))
    )
    (net (code "70") (name "Net-(L74-DOUT)") (class "Default")
      (node (ref "L74") (pin "2-DOUT") (pinfunction "DOUT_2-DOUT") (pintype "output"))
      (node (ref "L75") (pin "4-DIN") (pinfunction "DIN_4-DIN") (pintype "input"))
    )
    (net (code "71") (name "Net-(L75-DOUT)") (class "Default")
      (node (ref "L75") (pin "2-DOUT") (pinfunction "DOUT_2-DOUT") (pintype "output"))
      (node (ref "L76") (pin "4-DIN") (pinfunction "DIN_4-DIN") (pintype "input"))
    )
    (net (code "72") (name "Net-(L76-DOUT)") (class "Default")
      (node (ref "L76") (pin "2-DOUT") (pinfunction "DOUT_2-DOUT") (pintype "output"))
      (node (ref "L77") (pin "4-DIN") (pinfunction "DIN_4-DIN") (pintype "input"))
    )
    (net (code "73") (name "Net-(L78-DOUT)") (class "Default")
      (node (ref "L78") (pin "2-DOUT") (pinfunction "DOUT_2-DOUT") (pintype "output"))
      (node (ref "L79") (pin "4-DIN") (pinfunction "DIN_4-DIN") (pintype "input"))
    )
    (net (code "74") (name "Net-(L79-DOUT)") (class "Default")
      (node (ref "L79") (pin "2-DOUT") (pinfunction "DOUT_2-DOUT") (pintype "output"))
      (node (ref "L80") (pin "4-DIN") (pinfunction "DIN_4-DIN") (pintype "input"))
    )
    (net (code "75") (name "Net-(L80-DOUT)") (class "Default")
      (node (ref "L80") (pin "2-DOUT") (pinfunction "DOUT_2-DOUT") (pintype "output"))
      (node (ref "L81") (pin "4-DIN") (pinfunction "DIN_4-DIN") (pintype "input"))
    )
    (net (code "76") (name "Net-(L81-DOUT)") (class "Default")
      (node (ref "L81") (pin "2-DOUT") (pinfunction "DOUT_2-DOUT") (pintype "output"))
      (node (ref "L82") (pin "4-DIN") (pinfunction "DIN_4-DIN") (pintype "input"))
    )
    (net (code "77") (name "Net-(L82-DOUT)") (class "Default")
      (node (ref "L82") (pin "2-DOUT") (pinfunction "DOUT_2-DOUT") (pintype "output"))
      (node (ref "L83") (pin "4-DIN") (pinfunction "DIN_4-DIN") (pintype "input"))
    )
    (net (code "78") (name "Net-(L83-DOUT)") (class "Default")
      (node (ref "L83") (pin "2-DOUT") (pinfunction "DOUT_2-DOUT") (pintype "output"))
      (node (ref "L84") (pin "4-DIN") (pinfunction "DIN_4-DIN") (pintype "input"))
    )
    (net (code "79") (name "Net-(L84-DOUT)") (class "Default")
      (node (ref "L84") (pin "2-DOUT") (pinfunction "DOUT_2-DOUT") (pintype "output"))
      (node (ref "L85") (pin "4-DIN") (pinfunction "DIN_4-DIN") (pintype "input"))
    )
    (net (code "80") (name "Net-(L85-DOUT)") (class "Default")
      (node (ref "L85") (pin "2-DOUT") (pinfunction "DOUT_2-DOUT") (pintype "output"))
      (node (ref "L86") (pin "4-DIN") (pinfunction "DIN_4-DIN") (pintype "input"))
    )
    (net (code "81") (name "Net-(L86-DOUT)") (class "Default")
      (node (ref "L86") (pin "2-DOUT") (pinfunction "DOUT_2-DOUT") (pintype "output"))
      (node (ref "L87") (pin "4-DIN") (pinfunction "DIN_4-DIN") (pintype "input"))
    )
    (net (code "82") (name "Net-(L87-DOUT)") (class "Default")
      (node (ref "L87") (pin "2-DOUT") (pinfunction "DOUT_2-DOUT") (pintype "output"))
      (node (ref "L88") (pin "4-DIN") (pinfunction "DIN_4-DIN") (pintype "input"))
    )
    (net (code "83") (name "Net-(L89-DOUT)") (class "Default")
      (node (ref "L89") (pin "2-DOUT") (pinfunction "DOUT_2-DOUT") (pintype "output"))
      (node (ref "L90") (pin "4-DIN") (pinfunction "DIN_4-DIN") (pintype "input"))
    )
    (net (code "84") (name "Net-(L90-DOUT)") (class "Default")
      (node (ref "L90") (pin "2-DOUT") (pinfunction "DOUT_2-DOUT") (pintype "output"))
      (node (ref "L91") (pin "4-DIN") (pinfunction "DIN_4-DIN") (pintype "input"))
    )
    (net (code "85") (name "Net-(L91-DOUT)") (class "Default")
      (node (ref "L91") (pin "2-DOUT") (pinfunction "DOUT_2-DOUT") (pintype "output"))
      (node (ref "L92") (pin "4-DIN") (pinfunction "DIN_4-DIN") (pintype "input"))
    )
    (net (code "86") (name "Net-(L92-DOUT)") (class "Default")
      (node (ref "L92") (pin "2-DOUT") (pinfunction "DOUT_2-DOUT") (pintype "output"))
      (node (ref "L93") (pin "4-DIN") (pinfunction "DIN_4-DIN") (pintype "input"))
    )
    (net (code "87") (name "Net-(L93-DOUT)") (class "Default")
      (node (ref "L93") (pin "2-DOUT") (pinfunction "DOUT_2-DOUT") (pintype "output"))
      (node (ref "L94") (pin "4-DIN") (pinfunction "DIN_4-DIN") (pintype "input"))
    )
    (net (code "88") (name "Net-(L94-DOUT)") (class "Default")
      (node (ref "L94") (pin "2-DOUT") (pinfunction "DOUT_2-DOUT") (pintype "output"))
      (node (ref "L95") (pin "4-DIN") (pinfunction "DIN_4-DIN") (pintype "input"))
    )
    (net (code "89") (name "Net-(L95-DOUT)") (class "Default")
      (node (ref "L95") (pin "2-DOUT") (pinfunction "DOUT_2-DOUT") (pintype "output"))
      (node (ref "L96") (pin "4-DIN") (pinfunction "DIN_4-DIN") (pintype "input"))
    )
    (net (code "90") (name "Net-(L96-DOUT)") (class "Default")
      (node (ref "L96") (pin "2-DOUT") (pinfunction "DOUT_2-DOUT") (pintype "output"))
      (node (ref "L97") (pin "4-DIN") (pinfunction "DIN_4-DIN") (pintype "input"))
    )
    (net (code "91") (name "Net-(L97-DOUT)") (class "Default")
      (node (ref "L97") (pin "2-DOUT") (pinfunction "DOUT_2-DOUT") (pintype "output"))
      (node (ref "L98") (pin "4-DIN") (pinfunction "DIN_4-DIN") (pintype "input"))
    )
    (net (code "92") (name "Net-(L98-DOUT)") (class "Default")
      (node (ref "L98") (pin "2-DOUT") (pinfunction "DOUT_2-DOUT") (pintype "output"))
      (node (ref "L99") (pin "4-DIN") (pinfunction "DIN_4-DIN") (pintype "input"))
    )
    (net (code "93") (name "Net-(L100-DOUT)") (class "Default")
      (node (ref "L100") (pin "2-DOUT") (pinfunction "DOUT_2-DOUT") (pintype "output"))
      (node (ref "L101") (pin "4-DIN") (pinfunction "DIN_4-DIN") (pintype "input"))
    )
    (net (code "94") (name "Net-(L101-DOUT)") (class "Default")
      (node (ref "L101") (pin "2-DOUT") (pinfunction "DOUT_2-DOUT") (pintype "output"))
      (node (ref "L102") (pin "4-DIN") (pinfunction "DIN_4-DIN") (pintype "input"))
    )
    (net (code "95") (name "Net-(L102-DOUT)") (class "Default")
      (node (ref "L102") (pin "2-DOUT") (pinfunction "DOUT_2-DOUT") (pintype "output"))
      (node (ref "L103") (pin "4-DIN") (pinfunction "DIN_4-DIN") (pintype "input"))
    )
    (net (code "96") (name "Net-(L103-DOUT)") (class "Default")
      (node (ref "L103") (pin "2-DOUT") (pinfunction "DOUT_2-DOUT") (pintype "output"))
      (node (ref "L104") (pin "4-DIN") (pinfunction "DIN_4-DIN") (pintype "input"))
    )
    (net (code "97") (name "Net-(L104-DOUT)") (class "Default")
      (node (ref "L104") (pin "2-DOUT") (pinfunction "DOUT_2-DOUT") (pintype "output"))
      (node (ref "L105") (pin "4-DIN") (pinfunction "DIN_4-DIN") (pintype "input"))
    )
    (net (code "98") (name "Net-(L105-DOUT)") (class "Default")
      (node (ref "L105") (pin "2-DOUT") (pinfunction "DOUT_2-DOUT") (pintype "output"))
      (node (ref "L106") (pin "4-DIN") (pinfunction "DIN_4-DIN") (pintype "input"))
    )
    (net (code "99") (name "Net-(L106-DOUT)") (class "Default")
      (node (ref "L106") (pin "2-DOUT") (pinfunction "DOUT_2-DOUT") (pintype "output"))
      (node (ref "L107") (pin "4-DIN") (pinfunction "DIN_4-DIN") (pintype "input"))
    )
    (net (code "100") (name "Net-(L107-DOUT)") (class "Default")
      (node (ref "L107") (pin "2-DOUT") (pinfunction "DOUT_2-DOUT") (pintype "output"))
      (node (ref "L108") (pin "4-DIN") (pinfunction "DIN_4-DIN") (pintype "input"))
    )
    (net (code "101") (name "Net-(L108-DOUT)") (class "Default")
      (node (ref "L108") (pin "2-DOUT") (pinfunction "DOUT_2-DOUT") (pintype "output"))
      (node (ref "L109") (pin "4-DIN") (pinfunction "DIN_4-DIN") (pintype "input"))
    )
    (net (code "102") (name "Net-(L109-DOUT)") (class "Default")
      (node (ref "L109") (pin "2-DOUT") (pinfunction "DOUT_2-DOUT") (pintype "output"))
      (node (ref "L110") (pin "4-DIN") (pinfunction "DIN_4-DIN") (pintype "input"))
    )
    (net (code "103") (name "Net-(S+1-X1)") (class "Default")
      (node (ref "Q1") (pin "1") (pinfunction "1_1") (pintype "passive"))
      (node (ref "S+1") (pin "1") (pinfunction "X1_1") (pintype "bidirectional"))
    )
    (net (code "104") (name "Net-(S+1-X2)") (class "Default")
      (node (ref "Q1") (pin "2") (pinfunction "2_2") (pintype "passive"))
      (node (ref "S+1") (pin "2") (pinfunction "X2_2") (pintype "bidirectional"))
    )
    (net (code "105") (name "unconnected-(L1-DIN-Pad4-DIN)") (class "Default")
      (node (ref "L1") (pin "4-DIN") (pinfunction "DIN_4-DIN") (pintype "input"))
    )
    (net (code "106") (name "unconnected-(L11-DOUT-Pad2-DOUT)") (class "Default")
      (node (ref "L11") (pin "2-DOUT") (pinfunction "DOUT_2-DOUT") (pintype "output"))
    )
    (net (code "107") (name "unconnected-(L12-DIN-Pad4-DIN)") (class "Default")
      (node (ref "L12") (pin "4-DIN") (pinfunction "DIN_4-DIN") (pintype "input"))
    )
    (net (code "108") (name "unconnected-(L22-DOUT-Pad2-DOUT)") (class "Default")
      (node (ref "L22") (pin "2-DOUT") (pinfunction "DOUT_2-DOUT") (pintype "output"))
    )
    (net (code "109") (name "unconnected-(L23-DIN-Pad4-DIN)") (class "Default")
      (node (ref "L23") (pin "4-DIN") (pinfunction "DIN_4-DIN") (pintype "input"))
    )
    (net (code "110") (name "unconnected-(L33-DOUT-Pad2-DOUT)") (class "Default")
      (node (ref "L33") (pin "2-DOUT") (pinfunction "DOUT_2-DOUT") (pintype "output"))
    )
    (net (code "111") (name "unconnected-(L34-DIN-Pad4-DIN)") (class "Default")
      (node (ref "L34") (pin "4-DIN") (pinfunction "DIN_4-DIN") (pintype "input"))
    )
    (net (code "112") (name "unconnected-(L44-DOUT-Pad2-DOUT)") (class "Default")
      (node (ref "L44") (pin "2-DOUT") (pinfunction "DOUT_2-DOUT") (pintype "output"))
    )
    (net (code "113") (name "unconnected-(L45-DIN-Pad4-DIN)") (class "Default")
      (node (ref "L45") (pin "4-DIN") (pinfunction "DIN_4-DIN") (pintype "input"))
    )
    (net (code "114") (name "unconnected-(L55-DOUT-Pad2-DOUT)") (class "Default")
      (node (ref "L55") (pin "2-DOUT") (pinfunction "DOUT_2-DOUT") (pintype "output"))
    )
    (net (code "115") (name "unconnected-(L56-DIN-Pad4-DIN)") (class "Default")
      (node (ref "L56") (pin "4-DIN") (pinfunction "DIN_4-DIN") (pintype "input"))
    )
    (net (code "116") (name "unconnected-(L66-DOUT-Pad2-DOUT)") (class "Default")
      (node (ref "L66") (pin "2-DOUT") (pinfunction "DOUT_2-DOUT") (pintype "output"))
    )
    (net (code "117") (name "unconnected-(L67-DIN-Pad4-DIN)") (class "Default")
      (node (ref "L67") (pin "4-DIN") (pinfunction "DIN_4-DIN") (pintype "input"))
    )
    (net (code "118") (name "unconnected-(L77-DOUT-Pad2-DOUT)") (class "Default")
      (node (ref "L77") (pin "2-DOUT") (pinfunction "DOUT_2-DOUT") (pintype "output"))
    )
    (net (code "119") (name "unconnected-(L78-DIN-Pad4-DIN)") (class "Default")
      (node (ref "L78") (pin "4-DIN") (pinfunction "DIN_4-DIN") (pintype "input"))
    )
    (net (code "120") (name "unconnected-(L88-DOUT-Pad2-DOUT)") (class "Default")
      (node (ref "L88") (pin "2-DOUT") (pinfunction "DOUT_2-DOUT") (pintype "output"))
    )
    (net (code "121") (name "unconnected-(L89-DIN-Pad4-DIN)") (class "Default")
      (node (ref "L89") (pin "4-DIN") (pinfunction "DIN_4-DIN") (pintype "input"))
    )
    (net (code "122") (name "unconnected-(L99-DOUT-Pad2-DOUT)") (class "Default")
      (node (ref "L99") (pin "2-DOUT") (pinfunction "DOUT_2-DOUT") (pintype "output"))
    )
    (net (code "123") (name "unconnected-(L100-DIN-Pad4-DIN)") (class "Default")
      (node (ref "L100") (pin "4-DIN") (pinfunction "DIN_4-DIN") (pintype "input"))
    )
    (net (code "124") (name "unconnected-(L110-DOUT-Pad2-DOUT)") (class "Default")
      (node (ref "L110") (pin "2-DOUT") (pinfunction "DOUT_2-DOUT") (pintype "output"))
    )
    (net (code "125") (name "unconnected-(S+1-SCL-Pad6)") (class "Default")
      (node (ref "S+1") (pin "6") (pinfunction "SCL_6") (pintype "bidirectional"))
    )
    (net (code "126") (name "unconnected-(S+1-SDA-Pad5)") (class "Default")
      (node (ref "S+1") (pin "5") (pinfunction "SDA_5") (pintype "bidirectional"))
    )
    (net (code "127") (name "unconnected-(S+1-SQW{slash}~{INTB}-Pad7)") (class "Default")
      (node (ref "S+1") (pin "7") (pinfunction "SQW/~{INTB}_7") (pintype "bidirectional"))
    )
    (net (code "128") (name "unconnected-(S+1-VCC-Pad8)") (class "Default")
      (node (ref "S+1") (pin "8") (pinfunction "VCC_8") (pintype "bidirectional"))
    )
    (net (code "129") (name "unconnected-(S+1-~{INTA}-Pad3)") (class "Default")
      (node (ref "S+1") (pin "3") (pinfunction "~{INTA}_3") (pintype "bidirectional"))
    )
    (net (code "130") (name "unconnected-(U$1-Pad1)") (class "Default")
      (node (ref "U$1") (pin "1") (pinfunction "1_1") (pintype "input"))
    )
    (net (code "131") (name "unconnected-(U$1-Pad2)") (class "Default")
      (node (ref "U$1") (pin "2") (pinfunction "2_2") (pintype "input"))
    )
    (net (code "132") (name "unconnected-(U$1-Pad3)") (class "Default")
      (node (ref "U$1") (pin "3") (pinfunction "3_3") (pintype "input"))
    )
    (net (code "133") (name "unconnected-(U$1-Pad4)") (class "Default")
      (node (ref "U$1") (pin "4") (pinfunction "4_4") (pintype "input"))
    )
  )
)
